# FPGA.net
KiCad netlist of a schematic drawn in Altium Designer
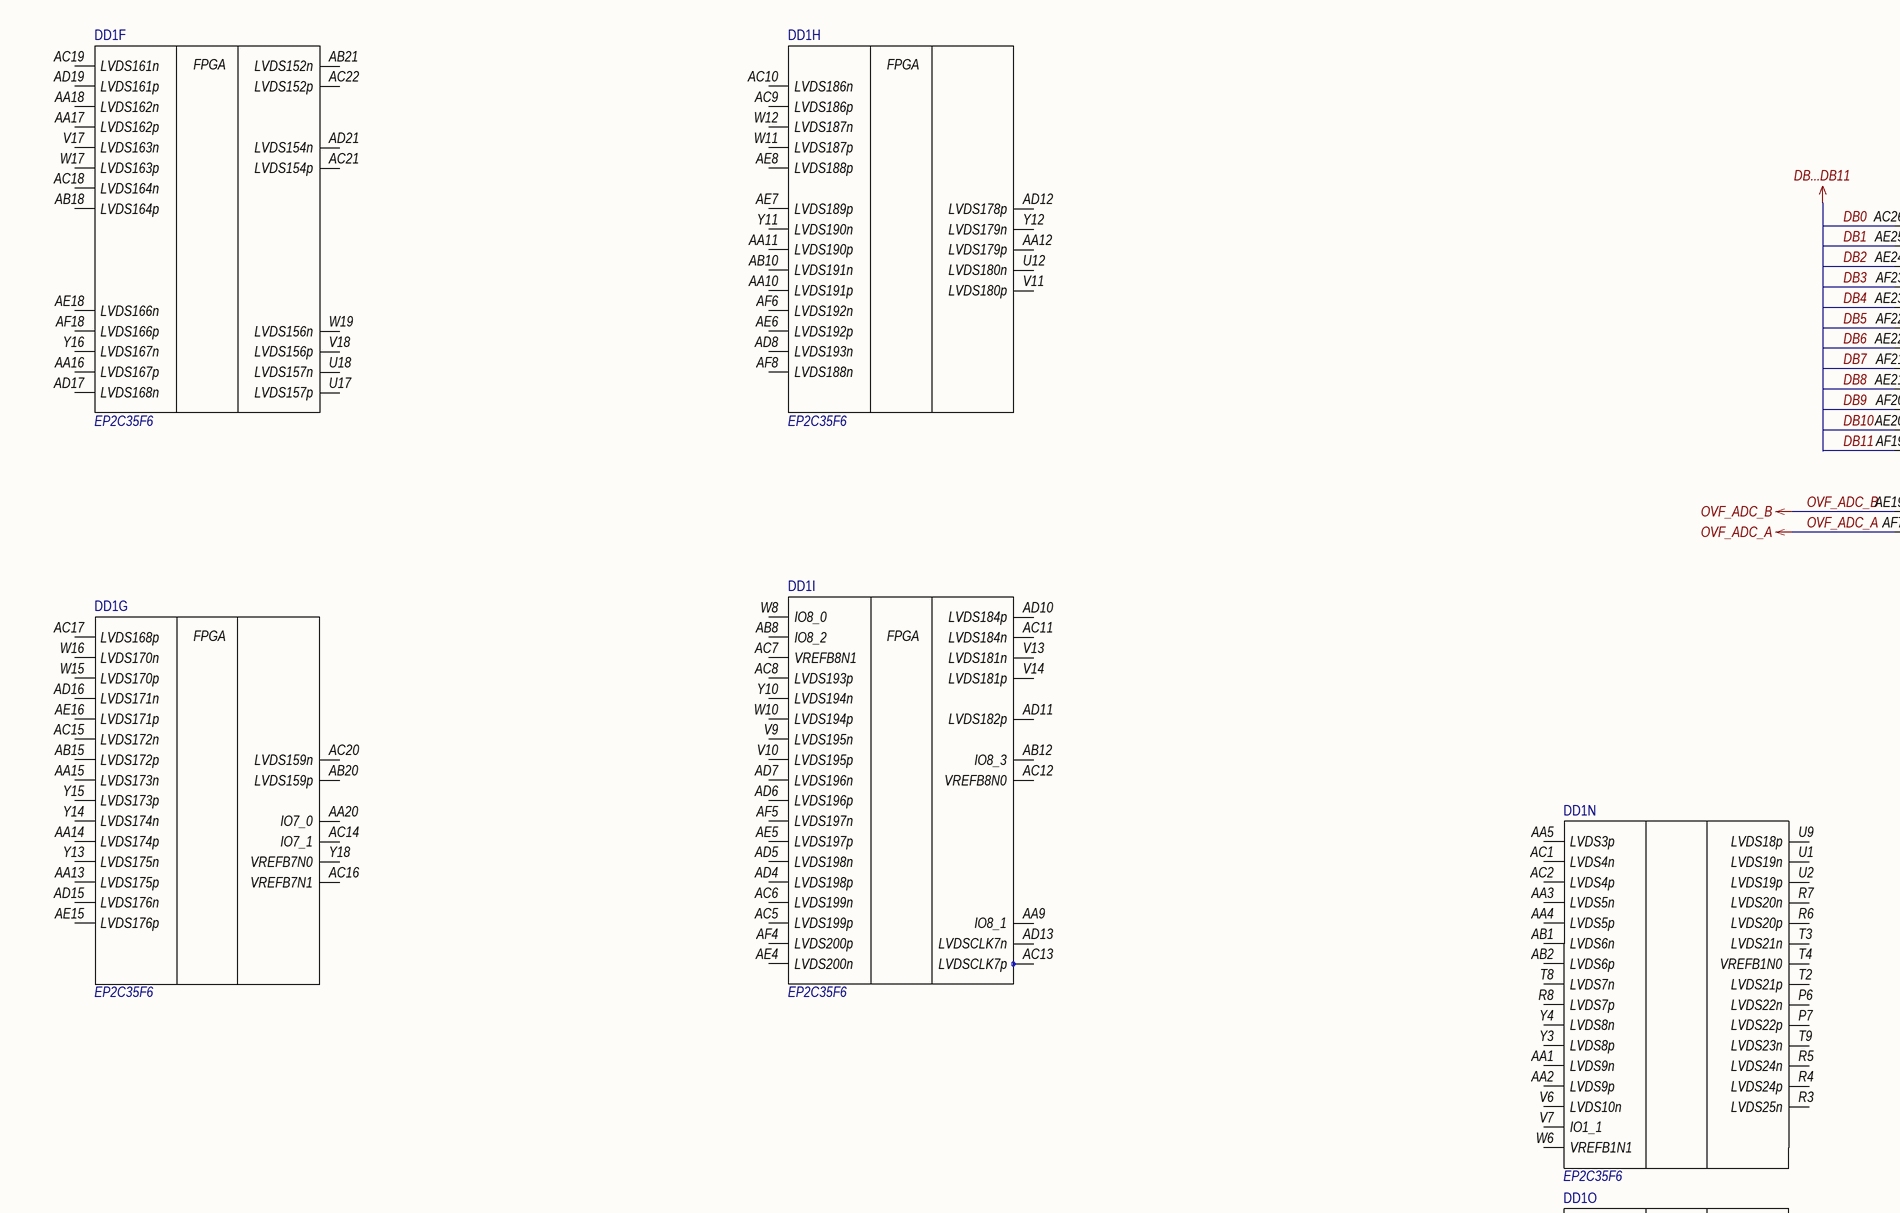
[diagram p0: FPGA.SchDoc, top left]
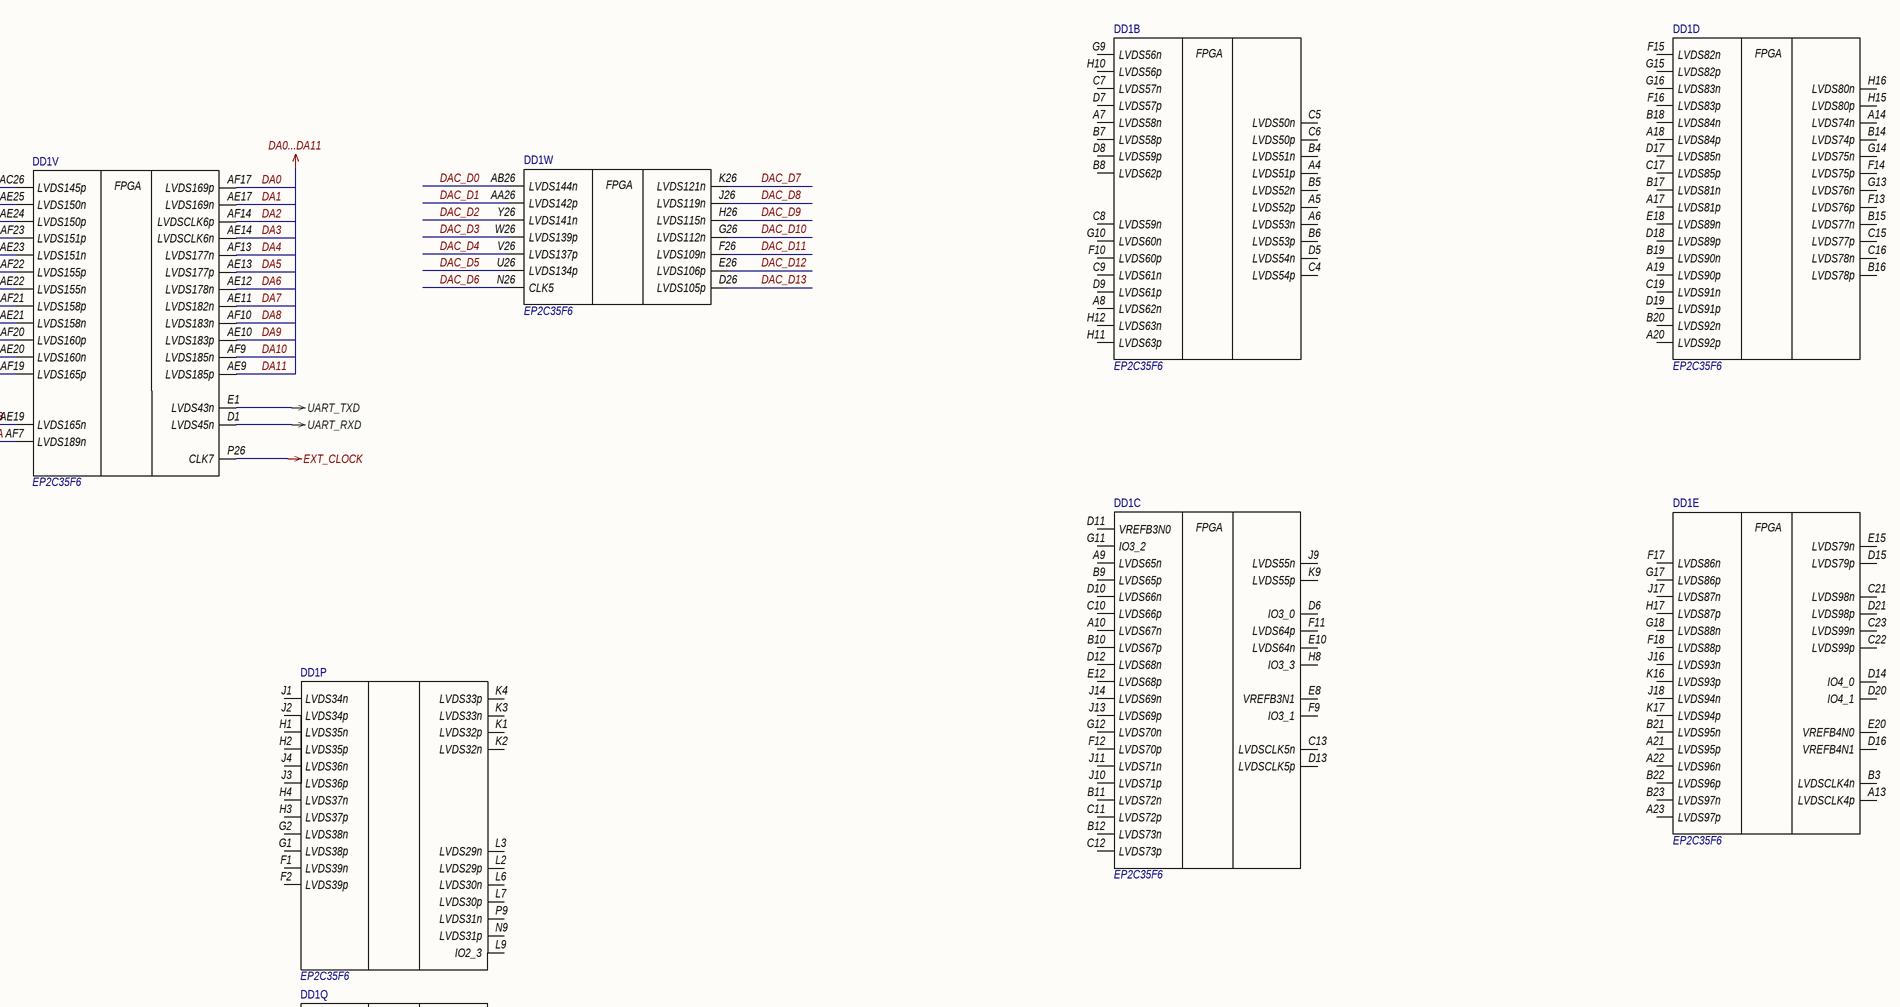
[diagram p1: FPGA.SchDoc, top right]
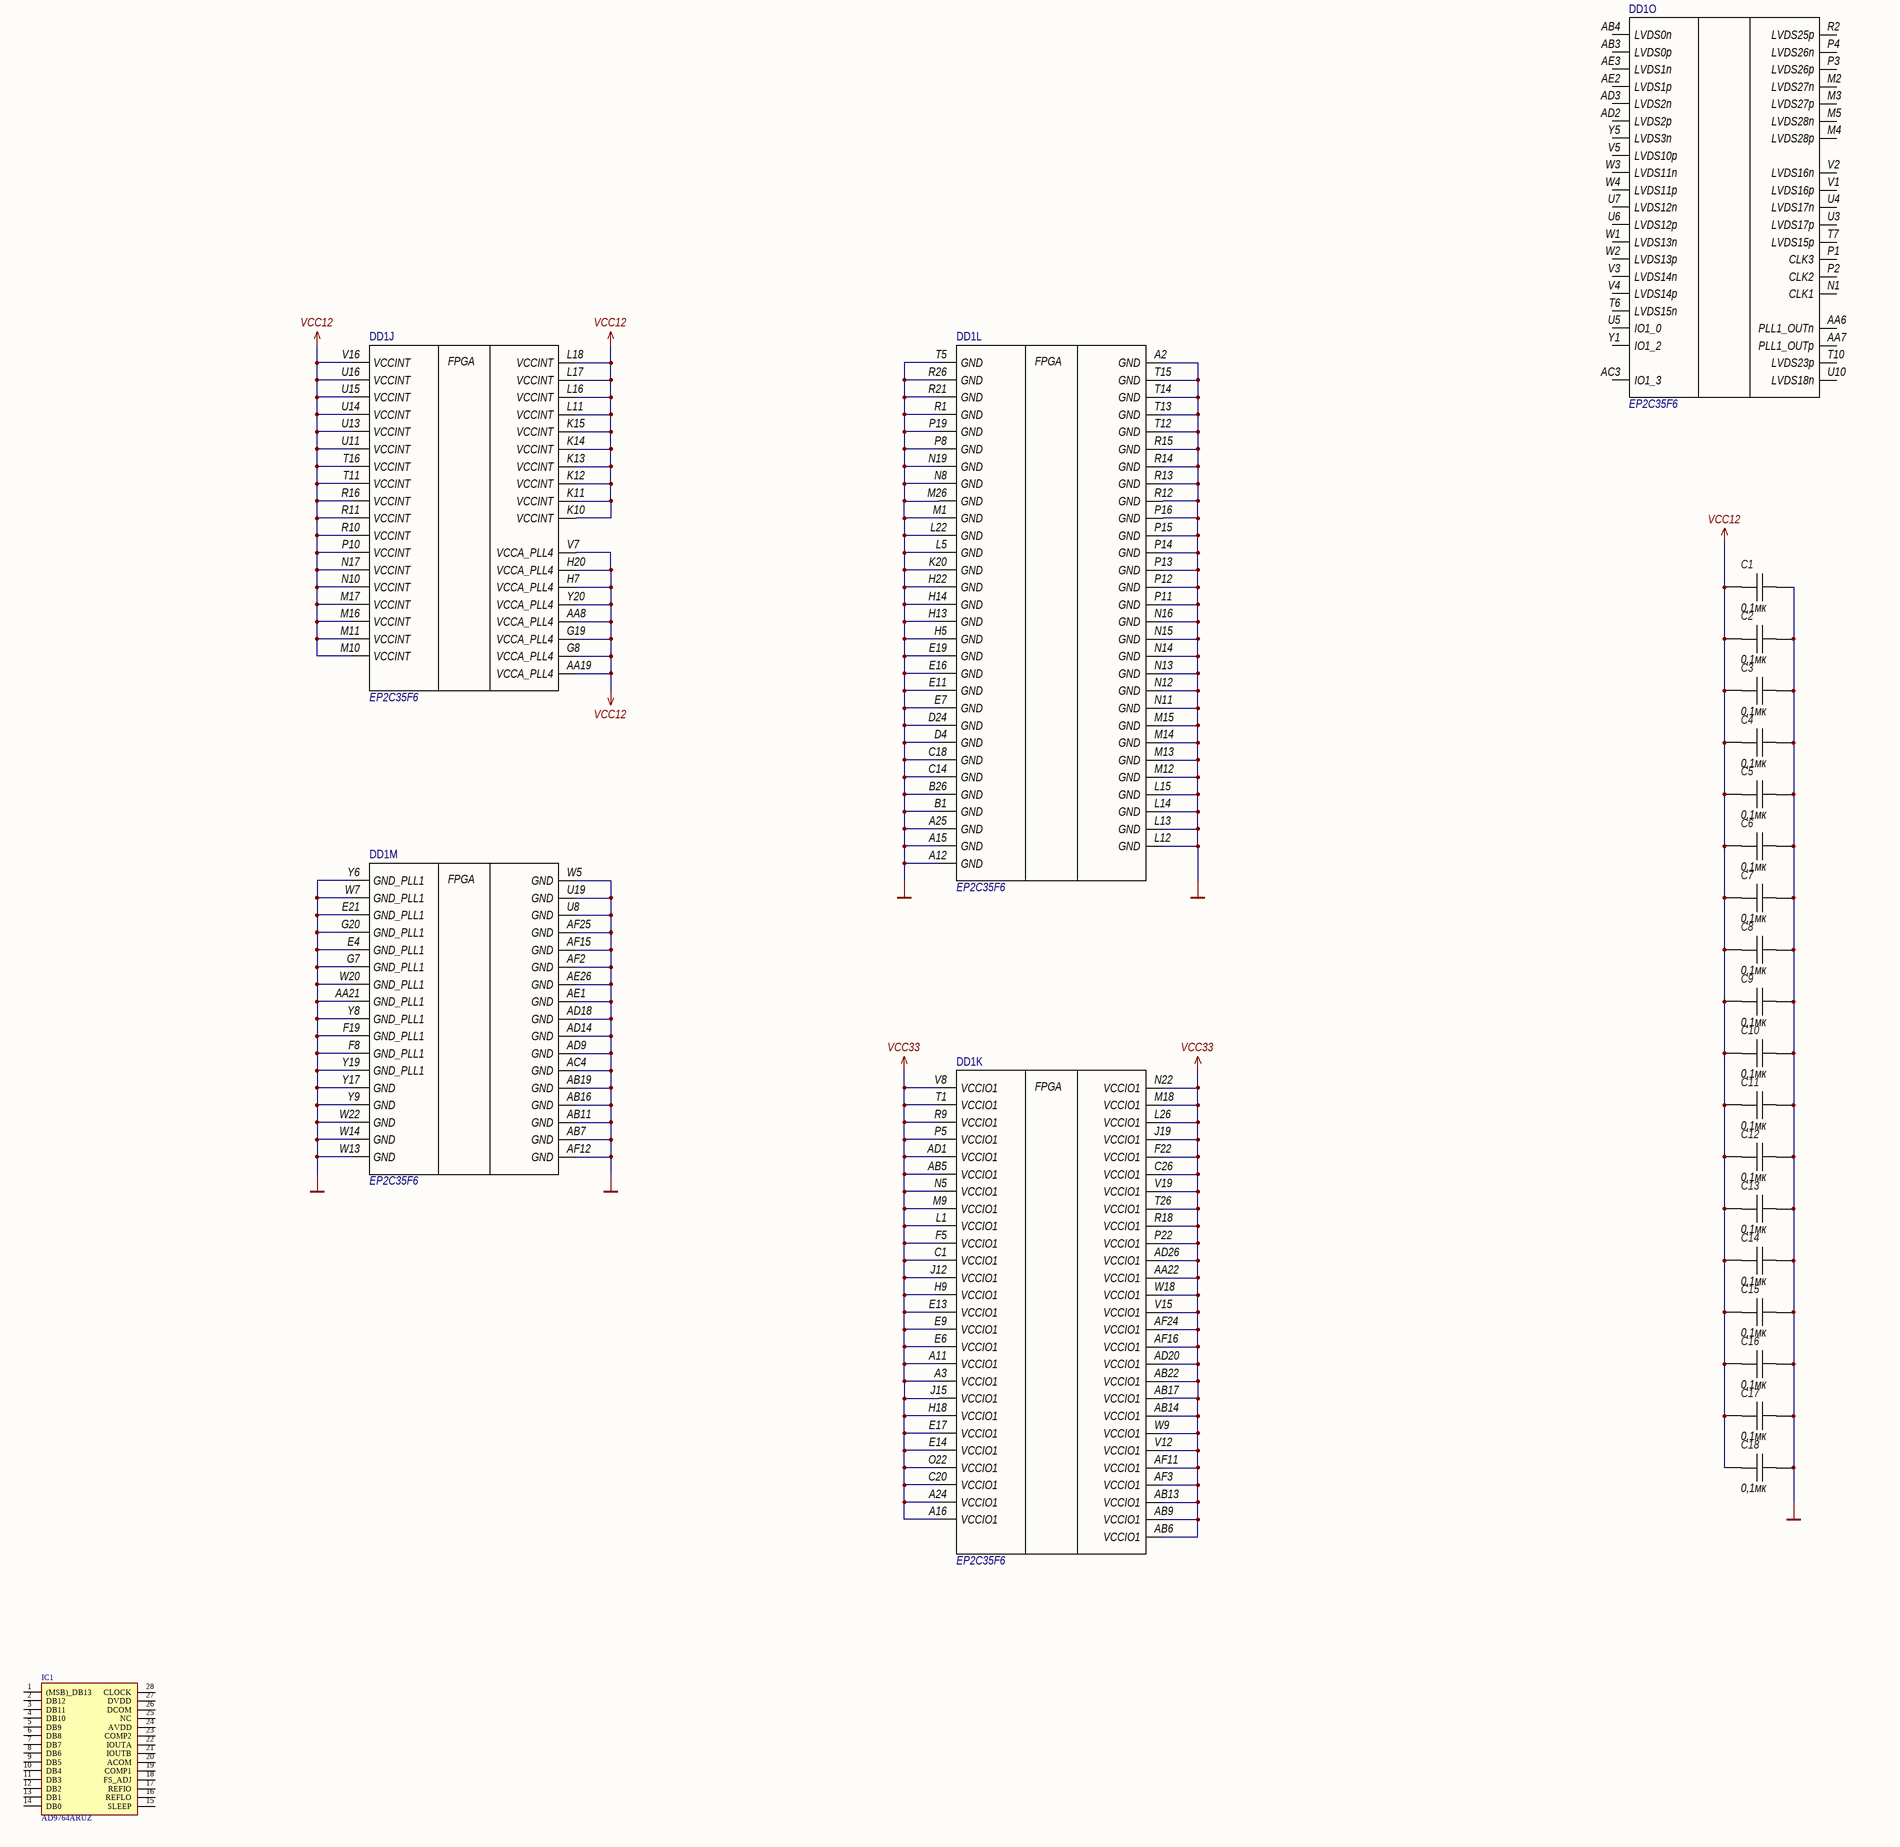
[diagram p2: FPGA.SchDoc, bottom left]
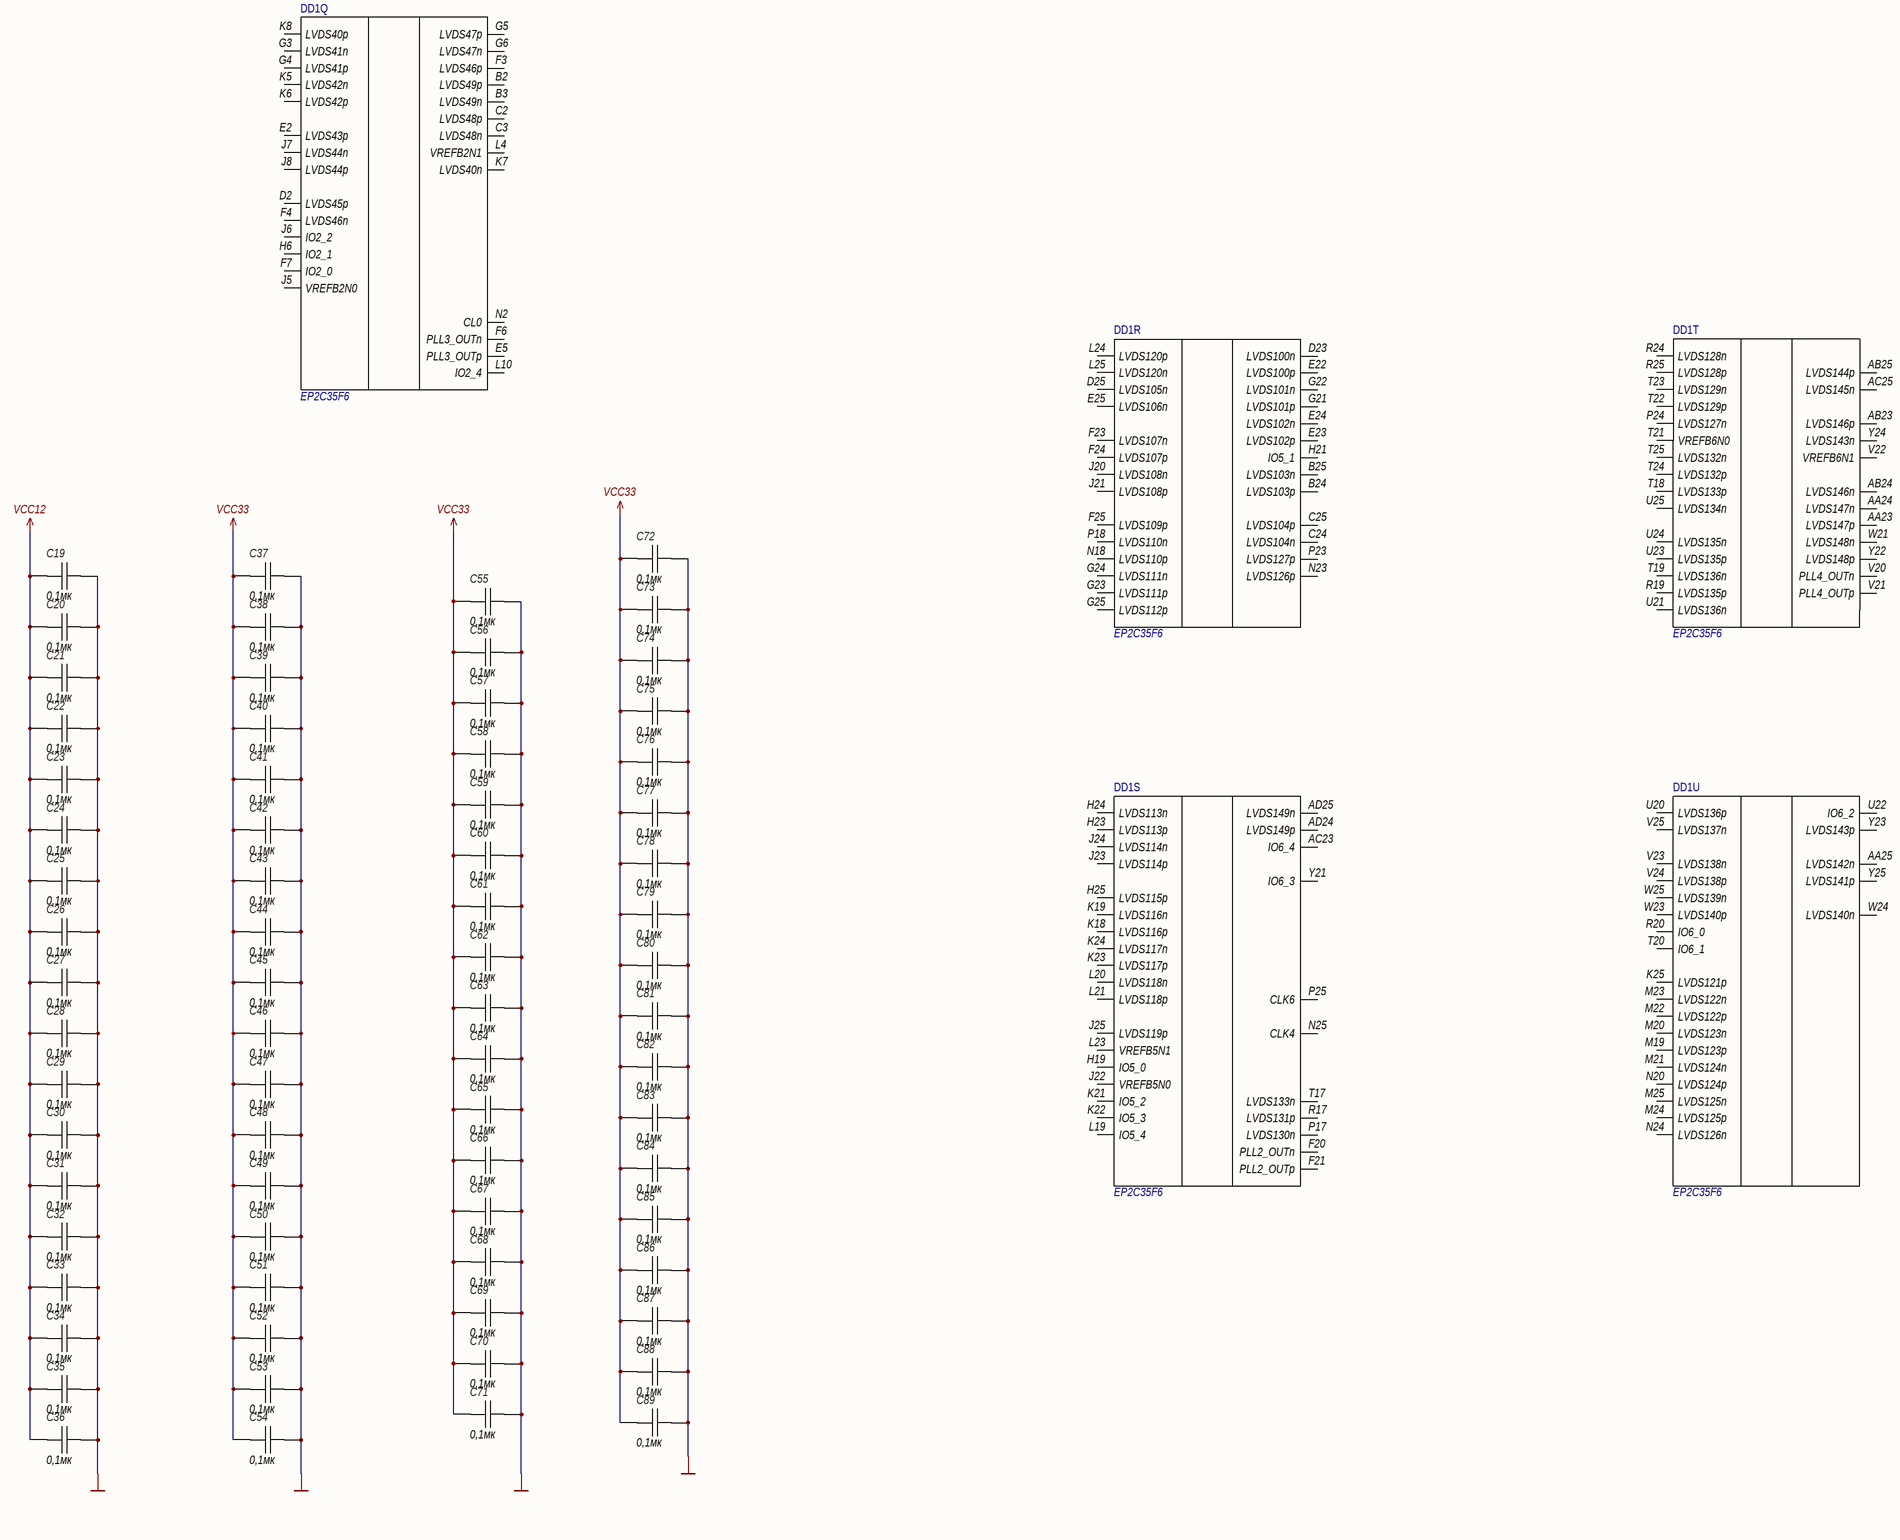
[diagram p3: FPGA.SchDoc, bottom right]

(export (version "E")
  (design (tool "Eeschema 10.0.6"))
  (components
    (comp (ref "C1")
      (value "0,1мк")
      (footprint "RESC1005X35N")
      (libsource (lib "FPGA_Automotibe_Radar_Lib") (part "Capacitor_0.1u"))
    )
    (comp (ref "C2")
      (value "0,1мк")
      (footprint "RESC1005X35N")
      (libsource (lib "FPGA_Automotibe_Radar_Lib") (part "Capacitor_0.1u"))
    )
    (comp (ref "C3")
      (value "0,1мк")
      (footprint "RESC1005X35N")
      (libsource (lib "FPGA_Automotibe_Radar_Lib") (part "Capacitor_0.1u"))
    )
    (comp (ref "C4")
      (value "0,1мк")
      (footprint "RESC1005X35N")
      (libsource (lib "FPGA_Automotibe_Radar_Lib") (part "Capacitor_0.1u"))
    )
    (comp (ref "C5")
      (value "0,1мк")
      (footprint "RESC1005X35N")
      (libsource (lib "FPGA_Automotibe_Radar_Lib") (part "Capacitor_0.1u"))
    )
    (comp (ref "C6")
      (value "0,1мк")
      (footprint "RESC1005X35N")
      (libsource (lib "FPGA_Automotibe_Radar_Lib") (part "Capacitor_0.1u"))
    )
    (comp (ref "C7")
      (value "0,1мк")
      (footprint "RESC1005X35N")
      (libsource (lib "FPGA_Automotibe_Radar_Lib") (part "Capacitor_0.1u"))
    )
    (comp (ref "C8")
      (value "0,1мк")
      (footprint "RESC1005X35N")
      (libsource (lib "FPGA_Automotibe_Radar_Lib") (part "Capacitor_0.1u"))
    )
    (comp (ref "C9")
      (value "0,1мк")
      (footprint "RESC1005X35N")
      (libsource (lib "FPGA_Automotibe_Radar_Lib") (part "Capacitor_0.1u"))
    )
    (comp (ref "C10")
      (value "0,1мк")
      (footprint "RESC1005X35N")
      (libsource (lib "FPGA_Automotibe_Radar_Lib") (part "Capacitor_0.1u"))
    )
    (comp (ref "C11")
      (value "0,1мк")
      (footprint "RESC1005X35N")
      (libsource (lib "FPGA_Automotibe_Radar_Lib") (part "Capacitor_0.1u"))
    )
    (comp (ref "C12")
      (value "0,1мк")
      (footprint "RESC1005X35N")
      (libsource (lib "FPGA_Automotibe_Radar_Lib") (part "Capacitor_0.1u"))
    )
    (comp (ref "C13")
      (value "0,1мк")
      (footprint "RESC1005X35N")
      (libsource (lib "FPGA_Automotibe_Radar_Lib") (part "Capacitor_0.1u"))
    )
    (comp (ref "C14")
      (value "0,1мк")
      (footprint "RESC1005X35N")
      (libsource (lib "FPGA_Automotibe_Radar_Lib") (part "Capacitor_0.1u"))
    )
    (comp (ref "C15")
      (value "0,1мк")
      (footprint "RESC1005X35N")
      (libsource (lib "FPGA_Automotibe_Radar_Lib") (part "Capacitor_0.1u"))
    )
    (comp (ref "C16")
      (value "0,1мк")
      (footprint "RESC1005X35N")
      (libsource (lib "FPGA_Automotibe_Radar_Lib") (part "Capacitor_0.1u"))
    )
    (comp (ref "C17")
      (value "0,1мк")
      (footprint "RESC1005X35N")
      (libsource (lib "FPGA_Automotibe_Radar_Lib") (part "Capacitor_0.1u"))
    )
    (comp (ref "C18")
      (value "0,1мк")
      (footprint "RESC1005X35N")
      (libsource (lib "FPGA_Automotibe_Radar_Lib") (part "Capacitor_0.1u"))
    )
    (comp (ref "C19")
      (value "0,1мк")
      (footprint "RESC1005X35N")
      (libsource (lib "FPGA_Automotibe_Radar_Lib") (part "Capacitor_0.1u"))
    )
    (comp (ref "C20")
      (value "0,1мк")
      (footprint "RESC1005X35N")
      (libsource (lib "FPGA_Automotibe_Radar_Lib") (part "Capacitor_0.1u"))
    )
    (comp (ref "C21")
      (value "0,1мк")
      (footprint "RESC1005X35N")
      (libsource (lib "FPGA_Automotibe_Radar_Lib") (part "Capacitor_0.1u"))
    )
    (comp (ref "C22")
      (value "0,1мк")
      (footprint "RESC1005X35N")
      (libsource (lib "FPGA_Automotibe_Radar_Lib") (part "Capacitor_0.1u"))
    )
    (comp (ref "C23")
      (value "0,1мк")
      (footprint "RESC1005X35N")
      (libsource (lib "FPGA_Automotibe_Radar_Lib") (part "Capacitor_0.1u"))
    )
    (comp (ref "C24")
      (value "0,1мк")
      (footprint "RESC1005X35N")
      (libsource (lib "FPGA_Automotibe_Radar_Lib") (part "Capacitor_0.1u"))
    )
    (comp (ref "C25")
      (value "0,1мк")
      (footprint "RESC1005X35N")
      (libsource (lib "FPGA_Automotibe_Radar_Lib") (part "Capacitor_0.1u"))
    )
    (comp (ref "C26")
      (value "0,1мк")
      (footprint "RESC1005X35N")
      (libsource (lib "FPGA_Automotibe_Radar_Lib") (part "Capacitor_0.1u"))
    )
    (comp (ref "C27")
      (value "0,1мк")
      (footprint "RESC1005X35N")
      (libsource (lib "FPGA_Automotibe_Radar_Lib") (part "Capacitor_0.1u"))
    )
    (comp (ref "C28")
      (value "0,1мк")
      (footprint "RESC1005X35N")
      (libsource (lib "FPGA_Automotibe_Radar_Lib") (part "Capacitor_0.1u"))
    )
    (comp (ref "C29")
      (value "0,1мк")
      (footprint "RESC1005X35N")
      (libsource (lib "FPGA_Automotibe_Radar_Lib") (part "Capacitor_0.1u"))
    )
    (comp (ref "C30")
      (value "0,1мк")
      (footprint "RESC1005X35N")
      (libsource (lib "FPGA_Automotibe_Radar_Lib") (part "Capacitor_0.1u"))
    )
    (comp (ref "C31")
      (value "0,1мк")
      (footprint "RESC1005X35N")
      (libsource (lib "FPGA_Automotibe_Radar_Lib") (part "Capacitor_0.1u"))
    )
    (comp (ref "C32")
      (value "0,1мк")
      (footprint "RESC1005X35N")
      (libsource (lib "FPGA_Automotibe_Radar_Lib") (part "Capacitor_0.1u"))
    )
    (comp (ref "C33")
      (value "0,1мк")
      (footprint "RESC1005X35N")
      (libsource (lib "FPGA_Automotibe_Radar_Lib") (part "Capacitor_0.1u"))
    )
    (comp (ref "C34")
      (value "0,1мк")
      (footprint "RESC1005X35N")
      (libsource (lib "FPGA_Automotibe_Radar_Lib") (part "Capacitor_0.1u"))
    )
    (comp (ref "C35")
      (value "0,1мк")
      (footprint "RESC1005X35N")
      (libsource (lib "FPGA_Automotibe_Radar_Lib") (part "Capacitor_0.1u"))
    )
    (comp (ref "C36")
      (value "0,1мк")
      (footprint "RESC1005X35N")
      (libsource (lib "FPGA_Automotibe_Radar_Lib") (part "Capacitor_0.1u"))
    )
    (comp (ref "C37")
      (value "0,1мк")
      (footprint "RESC1005X35N")
      (libsource (lib "FPGA_Automotibe_Radar_Lib") (part "Capacitor_0.1u"))
    )
    (comp (ref "C38")
      (value "0,1мк")
      (footprint "RESC1005X35N")
      (libsource (lib "FPGA_Automotibe_Radar_Lib") (part "Capacitor_0.1u"))
    )
    (comp (ref "C39")
      (value "0,1мк")
      (footprint "RESC1005X35N")
      (libsource (lib "FPGA_Automotibe_Radar_Lib") (part "Capacitor_0.1u"))
    )
    (comp (ref "C40")
      (value "0,1мк")
      (footprint "RESC1005X35N")
      (libsource (lib "FPGA_Automotibe_Radar_Lib") (part "Capacitor_0.1u"))
    )
    (comp (ref "C41")
      (value "0,1мк")
      (footprint "RESC1005X35N")
      (libsource (lib "FPGA_Automotibe_Radar_Lib") (part "Capacitor_0.1u"))
    )
    (comp (ref "C42")
      (value "0,1мк")
      (footprint "RESC1005X35N")
      (libsource (lib "FPGA_Automotibe_Radar_Lib") (part "Capacitor_0.1u"))
    )
    (comp (ref "C43")
      (value "0,1мк")
      (footprint "RESC1005X35N")
      (libsource (lib "FPGA_Automotibe_Radar_Lib") (part "Capacitor_0.1u"))
    )
    (comp (ref "C44")
      (value "0,1мк")
      (footprint "RESC1005X35N")
      (libsource (lib "FPGA_Automotibe_Radar_Lib") (part "Capacitor_0.1u"))
    )
    (comp (ref "C45")
      (value "0,1мк")
      (footprint "RESC1005X35N")
      (libsource (lib "FPGA_Automotibe_Radar_Lib") (part "Capacitor_0.1u"))
    )
    (comp (ref "C46")
      (value "0,1мк")
      (footprint "RESC1005X35N")
      (libsource (lib "FPGA_Automotibe_Radar_Lib") (part "Capacitor_0.1u"))
    )
    (comp (ref "C47")
      (value "0,1мк")
      (footprint "RESC1005X35N")
      (libsource (lib "FPGA_Automotibe_Radar_Lib") (part "Capacitor_0.1u"))
    )
    (comp (ref "C48")
      (value "0,1мк")
      (footprint "RESC1005X35N")
      (libsource (lib "FPGA_Automotibe_Radar_Lib") (part "Capacitor_0.1u"))
    )
    (comp (ref "C49")
      (value "0,1мк")
      (footprint "RESC1005X35N")
      (libsource (lib "FPGA_Automotibe_Radar_Lib") (part "Capacitor_0.1u"))
    )
    (comp (ref "C50")
      (value "0,1мк")
      (footprint "RESC1005X35N")
      (libsource (lib "FPGA_Automotibe_Radar_Lib") (part "Capacitor_0.1u"))
    )
    (comp (ref "C51")
      (value "0,1мк")
      (footprint "RESC1005X35N")
      (libsource (lib "FPGA_Automotibe_Radar_Lib") (part "Capacitor_0.1u"))
    )
    (comp (ref "C52")
      (value "0,1мк")
      (footprint "RESC1005X35N")
      (libsource (lib "FPGA_Automotibe_Radar_Lib") (part "Capacitor_0.1u"))
    )
    (comp (ref "C53")
      (value "0,1мк")
      (footprint "RESC1005X35N")
      (libsource (lib "FPGA_Automotibe_Radar_Lib") (part "Capacitor_0.1u"))
    )
    (comp (ref "C54")
      (value "0,1мк")
      (footprint "RESC1005X35N")
      (libsource (lib "FPGA_Automotibe_Radar_Lib") (part "Capacitor_0.1u"))
    )
    (comp (ref "C55")
      (value "0,1мк")
      (footprint "RESC1005X35N")
      (libsource (lib "FPGA_Automotibe_Radar_Lib") (part "Capacitor_0.1u"))
    )
    (comp (ref "C56")
      (value "0,1мк")
      (footprint "RESC1005X35N")
      (libsource (lib "FPGA_Automotibe_Radar_Lib") (part "Capacitor_0.1u"))
    )
    (comp (ref "C57")
      (value "0,1мк")
      (footprint "RESC1005X35N")
      (libsource (lib "FPGA_Automotibe_Radar_Lib") (part "Capacitor_0.1u"))
    )
    (comp (ref "C58")
      (value "0,1мк")
      (footprint "RESC1005X35N")
      (libsource (lib "FPGA_Automotibe_Radar_Lib") (part "Capacitor_0.1u"))
    )
    (comp (ref "C59")
      (value "0,1мк")
      (footprint "RESC1005X35N")
      (libsource (lib "FPGA_Automotibe_Radar_Lib") (part "Capacitor_0.1u"))
    )
    (comp (ref "C60")
      (value "0,1мк")
      (footprint "RESC1005X35N")
      (libsource (lib "FPGA_Automotibe_Radar_Lib") (part "Capacitor_0.1u"))
    )
    (comp (ref "C61")
      (value "0,1мк")
      (footprint "RESC1005X35N")
      (libsource (lib "FPGA_Automotibe_Radar_Lib") (part "Capacitor_0.1u"))
    )
    (comp (ref "C62")
      (value "0,1мк")
      (footprint "RESC1005X35N")
      (libsource (lib "FPGA_Automotibe_Radar_Lib") (part "Capacitor_0.1u"))
    )
    (comp (ref "C63")
      (value "0,1мк")
      (footprint "RESC1005X35N")
      (libsource (lib "FPGA_Automotibe_Radar_Lib") (part "Capacitor_0.1u"))
    )
    (comp (ref "C64")
      (value "0,1мк")
      (footprint "RESC1005X35N")
      (libsource (lib "FPGA_Automotibe_Radar_Lib") (part "Capacitor_0.1u"))
    )
    (comp (ref "C65")
      (value "0,1мк")
      (footprint "RESC1005X35N")
      (libsource (lib "FPGA_Automotibe_Radar_Lib") (part "Capacitor_0.1u"))
    )
    (comp (ref "C66")
      (value "0,1мк")
      (footprint "RESC1005X35N")
      (libsource (lib "FPGA_Automotibe_Radar_Lib") (part "Capacitor_0.1u"))
    )
    (comp (ref "C67")
      (value "0,1мк")
      (footprint "RESC1005X35N")
      (libsource (lib "FPGA_Automotibe_Radar_Lib") (part "Capacitor_0.1u"))
    )
    (comp (ref "C68")
      (value "0,1мк")
      (footprint "RESC1005X35N")
      (libsource (lib "FPGA_Automotibe_Radar_Lib") (part "Capacitor_0.1u"))
    )
    (comp (ref "C69")
      (value "0,1мк")
      (footprint "RESC1005X35N")
      (libsource (lib "FPGA_Automotibe_Radar_Lib") (part "Capacitor_0.1u"))
    )
    (comp (ref "C70")
      (value "0,1мк")
      (footprint "RESC1005X35N")
      (libsource (lib "FPGA_Automotibe_Radar_Lib") (part "Capacitor_0.1u"))
    )
    (comp (ref "C71")
      (value "0,1мк")
      (footprint "RESC1005X35N")
      (libsource (lib "FPGA_Automotibe_Radar_Lib") (part "Capacitor_0.1u"))
    )
    (comp (ref "C72")
      (value "0,1мк")
      (footprint "RESC1005X35N")
      (libsource (lib "FPGA_Automotibe_Radar_Lib") (part "Capacitor_0.1u"))
    )
    (comp (ref "C73")
      (value "0,1мк")
      (footprint "RESC1005X35N")
      (libsource (lib "FPGA_Automotibe_Radar_Lib") (part "Capacitor_0.1u"))
    )
    (comp (ref "C74")
      (value "0,1мк")
      (footprint "RESC1005X35N")
      (libsource (lib "FPGA_Automotibe_Radar_Lib") (part "Capacitor_0.1u"))
    )
    (comp (ref "C75")
      (value "0,1мк")
      (footprint "RESC1005X35N")
      (libsource (lib "FPGA_Automotibe_Radar_Lib") (part "Capacitor_0.1u"))
    )
    (comp (ref "C76")
      (value "0,1мк")
      (footprint "RESC1005X35N")
      (libsource (lib "FPGA_Automotibe_Radar_Lib") (part "Capacitor_0.1u"))
    )
    (comp (ref "C77")
      (value "0,1мк")
      (footprint "RESC1005X35N")
      (libsource (lib "FPGA_Automotibe_Radar_Lib") (part "Capacitor_0.1u"))
    )
    (comp (ref "C78")
      (value "0,1мк")
      (footprint "RESC1005X35N")
      (libsource (lib "FPGA_Automotibe_Radar_Lib") (part "Capacitor_0.1u"))
    )
    (comp (ref "C79")
      (value "0,1мк")
      (footprint "RESC1005X35N")
      (libsource (lib "FPGA_Automotibe_Radar_Lib") (part "Capacitor_0.1u"))
    )
    (comp (ref "C80")
      (value "0,1мк")
      (footprint "RESC1005X35N")
      (libsource (lib "FPGA_Automotibe_Radar_Lib") (part "Capacitor_0.1u"))
    )
    (comp (ref "C81")
      (value "0,1мк")
      (footprint "RESC1005X35N")
      (libsource (lib "FPGA_Automotibe_Radar_Lib") (part "Capacitor_0.1u"))
    )
    (comp (ref "C82")
      (value "0,1мк")
      (footprint "RESC1005X35N")
      (libsource (lib "FPGA_Automotibe_Radar_Lib") (part "Capacitor_0.1u"))
    )
    (comp (ref "C83")
      (value "0,1мк")
      (footprint "RESC1005X35N")
      (libsource (lib "FPGA_Automotibe_Radar_Lib") (part "Capacitor_0.1u"))
    )
    (comp (ref "C84")
      (value "0,1мк")
      (footprint "RESC1005X35N")
      (libsource (lib "FPGA_Automotibe_Radar_Lib") (part "Capacitor_0.1u"))
    )
    (comp (ref "C85")
      (value "0,1мк")
      (footprint "RESC1005X35N")
      (libsource (lib "FPGA_Automotibe_Radar_Lib") (part "Capacitor_0.1u"))
    )
    (comp (ref "C86")
      (value "0,1мк")
      (footprint "RESC1005X35N")
      (libsource (lib "FPGA_Automotibe_Radar_Lib") (part "Capacitor_0.1u"))
    )
    (comp (ref "C87")
      (value "0,1мк")
      (footprint "RESC1005X35N")
      (libsource (lib "FPGA_Automotibe_Radar_Lib") (part "Capacitor_0.1u"))
    )
    (comp (ref "C88")
      (value "0,1мк")
      (footprint "RESC1005X35N")
      (libsource (lib "FPGA_Automotibe_Radar_Lib") (part "Capacitor_0.1u"))
    )
    (comp (ref "C89")
      (value "0,1мк")
      (footprint "RESC1005X35N")
      (libsource (lib "FPGA_Automotibe_Radar_Lib") (part "Capacitor_0.1u"))
    )
    (comp (ref "DD1")
      (value "EP2C35F6")
      (footprint "BGA672CP100_26X26_2700X2700X240B60N")
      (libsource (lib "FPGA_Automotibe_Radar_Lib") (part "PLIS"))
    )
    (comp (ref "IC1")
      (value "AD9764ARUZ")
      (footprint "SamacSys:SOP65P640X120-28N")
      (description "Integrated Circuit")
      (fields (field (name "MOUSER PART NUMBER") "584-AD9764ARUZ"))
      (libsource (lib "*") (part "AD9764ARUZ"))
    )
  )
  (nets
    (net (code "1") (name "/DA0") (class "Default")
      (node (ref "DD1") (pin "AF17") (pinfunction "LVDS169p_AF17") (pintype "passive"))
    )
    (net (code "2") (name "/DA1") (class "Default")
      (node (ref "DD1") (pin "AE17") (pinfunction "LVDS169n_AE17") (pintype "passive"))
    )
    (net (code "3") (name "/DA2") (class "Default")
      (node (ref "DD1") (pin "AF14") (pinfunction "LVDSCLK6p_AF14") (pintype "passive"))
    )
    (net (code "4") (name "/DA3") (class "Default")
      (node (ref "DD1") (pin "AE14") (pinfunction "LVDSCLK6n_AE14") (pintype "passive"))
    )
    (net (code "5") (name "/DA4") (class "Default")
      (node (ref "DD1") (pin "AF13") (pinfunction "LVDS177n_AF13") (pintype "passive"))
    )
    (net (code "6") (name "/DA5") (class "Default")
      (node (ref "DD1") (pin "AE13") (pinfunction "LVDS177p_AE13") (pintype "passive"))
    )
    (net (code "7") (name "/DA6") (class "Default")
      (node (ref "DD1") (pin "AE12") (pinfunction "LVDS178n_AE12") (pintype "passive"))
    )
    (net (code "8") (name "/DA7") (class "Default")
      (node (ref "DD1") (pin "AE11") (pinfunction "LVDS182n_AE11") (pintype "passive"))
    )
    (net (code "9") (name "/DA8") (class "Default")
      (node (ref "DD1") (pin "AF10") (pinfunction "LVDS183n_AF10") (pintype "passive"))
    )
    (net (code "10") (name "/DA9") (class "Default")
      (node (ref "DD1") (pin "AE10") (pinfunction "LVDS183p_AE10") (pintype "passive"))
    )
    (net (code "11") (name "/DA10") (class "Default")
      (node (ref "DD1") (pin "AF9") (pinfunction "LVDS185n_AF9") (pintype "passive"))
    )
    (net (code "12") (name "/DA11") (class "Default")
      (node (ref "DD1") (pin "AE9") (pinfunction "LVDS185p_AE9") (pintype "passive"))
    )
    (net (code "13") (name "/DAC_D0") (class "Default")
      (node (ref "DD1") (pin "AB26") (pinfunction "LVDS144n_AB26") (pintype "passive"))
    )
    (net (code "14") (name "/DAC_D1") (class "Default")
      (node (ref "DD1") (pin "AA26") (pinfunction "LVDS142p_AA26") (pintype "passive"))
    )
    (net (code "15") (name "/DAC_D2") (class "Default")
      (node (ref "DD1") (pin "Y26") (pinfunction "LVDS141n_Y26") (pintype "passive"))
    )
    (net (code "16") (name "/DAC_D3") (class "Default")
      (node (ref "DD1") (pin "W26") (pinfunction "LVDS139p_W26") (pintype "passive"))
    )
    (net (code "17") (name "/DAC_D4") (class "Default")
      (node (ref "DD1") (pin "V26") (pinfunction "LVDS137p_V26") (pintype "passive"))
    )
    (net (code "18") (name "/DAC_D5") (class "Default")
      (node (ref "DD1") (pin "U26") (pinfunction "LVDS134p_U26") (pintype "passive"))
    )
    (net (code "19") (name "/DAC_D6") (class "Default")
      (node (ref "DD1") (pin "N26") (pinfunction "CLK5_N26") (pintype "passive"))
    )
    (net (code "20") (name "/DAC_D7") (class "Default")
      (node (ref "DD1") (pin "K26") (pinfunction "LVDS121n_K26") (pintype "passive"))
    )
    (net (code "21") (name "/DAC_D8") (class "Default")
      (node (ref "DD1") (pin "J26") (pinfunction "LVDS119n_J26") (pintype "passive"))
    )
    (net (code "22") (name "/DAC_D9") (class "Default")
      (node (ref "DD1") (pin "H26") (pinfunction "LVDS115n_H26") (pintype "passive"))
    )
    (net (code "23") (name "/DAC_D10") (class "Default")
      (node (ref "DD1") (pin "G26") (pinfunction "LVDS112n_G26") (pintype "passive"))
    )
    (net (code "24") (name "/DAC_D11") (class "Default")
      (node (ref "DD1") (pin "F26") (pinfunction "LVDS109n_F26") (pintype "passive"))
    )
    (net (code "25") (name "/DAC_D12") (class "Default")
      (node (ref "DD1") (pin "E26") (pinfunction "LVDS106p_E26") (pintype "passive"))
    )
    (net (code "26") (name "/DAC_D13") (class "Default")
      (node (ref "DD1") (pin "D26") (pinfunction "LVDS105p_D26") (pintype "passive"))
    )
    (net (code "27") (name "/DB0") (class "Default")
      (node (ref "DD1") (pin "AC26") (pinfunction "LVDS145p_AC26") (pintype "passive"))
    )
    (net (code "28") (name "/DB1") (class "Default")
      (node (ref "DD1") (pin "AE25") (pinfunction "LVDS150n_AE25") (pintype "passive"))
    )
    (net (code "29") (name "/DB2") (class "Default")
      (node (ref "DD1") (pin "AE24") (pinfunction "LVDS150p_AE24") (pintype "passive"))
    )
    (net (code "30") (name "/DB3") (class "Default")
      (node (ref "DD1") (pin "AF23") (pinfunction "LVDS151p_AF23") (pintype "passive"))
    )
    (net (code "31") (name "/DB4") (class "Default")
      (node (ref "DD1") (pin "AE23") (pinfunction "LVDS151n_AE23") (pintype "passive"))
    )
    (net (code "32") (name "/DB5") (class "Default")
      (node (ref "DD1") (pin "AF22") (pinfunction "LVDS155p_AF22") (pintype "passive"))
    )
    (net (code "33") (name "/DB6") (class "Default")
      (node (ref "DD1") (pin "AE22") (pinfunction "LVDS155n_AE22") (pintype "passive"))
    )
    (net (code "34") (name "/DB7") (class "Default")
      (node (ref "DD1") (pin "AF21") (pinfunction "LVDS158p_AF21") (pintype "passive"))
    )
    (net (code "35") (name "/DB8") (class "Default")
      (node (ref "DD1") (pin "AE21") (pinfunction "LVDS158n_AE21") (pintype "passive"))
    )
    (net (code "36") (name "/DB9") (class "Default")
      (node (ref "DD1") (pin "AF20") (pinfunction "LVDS160p_AF20") (pintype "passive"))
    )
    (net (code "37") (name "/DB10") (class "Default")
      (node (ref "DD1") (pin "AE20") (pinfunction "LVDS160n_AE20") (pintype "passive"))
    )
    (net (code "38") (name "/DB11") (class "Default")
      (node (ref "DD1") (pin "AF19") (pinfunction "LVDS165p_AF19") (pintype "passive"))
    )
    (net (code "41") (name "EXT_CLOCK") (class "Default")
      (node (ref "DD1") (pin "P26") (pinfunction "CLK7_P26") (pintype "passive"))
    )
    (net (code "42") (name "GND") (class "Default")
      (node (ref "C1") (pin "2") (pinfunction "2_2") (pintype "passive"))
      (node (ref "C10") (pin "2") (pinfunction "2_2") (pintype "passive"))
      (node (ref "C11") (pin "2") (pinfunction "2_2") (pintype "passive"))
      (node (ref "C12") (pin "2") (pinfunction "2_2") (pintype "passive"))
      (node (ref "C13") (pin "2") (pinfunction "2_2") (pintype "passive"))
      (node (ref "C14") (pin "2") (pinfunction "2_2") (pintype "passive"))
      (node (ref "C15") (pin "2") (pinfunction "2_2") (pintype "passive"))
      (node (ref "C16") (pin "2") (pinfunction "2_2") (pintype "passive"))
      (node (ref "C17") (pin "2") (pinfunction "2_2") (pintype "passive"))
      (node (ref "C18") (pin "2") (pinfunction "2_2") (pintype "passive"))
      (node (ref "C19") (pin "2") (pinfunction "2_2") (pintype "passive"))
      (node (ref "C2") (pin "2") (pinfunction "2_2") (pintype "passive"))
      (node (ref "C20") (pin "2") (pinfunction "2_2") (pintype "passive"))
      (node (ref "C21") (pin "2") (pinfunction "2_2") (pintype "passive"))
      (node (ref "C22") (pin "2") (pinfunction "2_2") (pintype "passive"))
      (node (ref "C23") (pin "2") (pinfunction "2_2") (pintype "passive"))
      (node (ref "C24") (pin "2") (pinfunction "2_2") (pintype "passive"))
      (node (ref "C25") (pin "2") (pinfunction "2_2") (pintype "passive"))
      (node (ref "C26") (pin "2") (pinfunction "2_2") (pintype "passive"))
      (node (ref "C27") (pin "2") (pinfunction "2_2") (pintype "passive"))
      (node (ref "C28") (pin "2") (pinfunction "2_2") (pintype "passive"))
      (node (ref "C29") (pin "2") (pinfunction "2_2") (pintype "passive"))
      (node (ref "C3") (pin "2") (pinfunction "2_2") (pintype "passive"))
      (node (ref "C30") (pin "2") (pinfunction "2_2") (pintype "passive"))
      (node (ref "C31") (pin "2") (pinfunction "2_2") (pintype "passive"))
      (node (ref "C32") (pin "2") (pinfunction "2_2") (pintype "passive"))
      (node (ref "C33") (pin "2") (pinfunction "2_2") (pintype "passive"))
      (node (ref "C34") (pin "2") (pinfunction "2_2") (pintype "passive"))
      (node (ref "C35") (pin "2") (pinfunction "2_2") (pintype "passive"))
      (node (ref "C36") (pin "2") (pinfunction "2_2") (pintype "passive"))
      (node (ref "C37") (pin "2") (pinfunction "2_2") (pintype "passive"))
      (node (ref "C38") (pin "2") (pinfunction "2_2") (pintype "passive"))
      (node (ref "C39") (pin "2") (pinfunction "2_2") (pintype "passive"))
      (node (ref "C4") (pin "2") (pinfunction "2_2") (pintype "passive"))
      (node (ref "C40") (pin "2") (pinfunction "2_2") (pintype "passive"))
      (node (ref "C41") (pin "2") (pinfunction "2_2") (pintype "passive"))
      (node (ref "C42") (pin "2") (pinfunction "2_2") (pintype "passive"))
      (node (ref "C43") (pin "2") (pinfunction "2_2") (pintype "passive"))
      (node (ref "C44") (pin "2") (pinfunction "2_2") (pintype "passive"))
      (node (ref "C45") (pin "2") (pinfunction "2_2") (pintype "passive"))
      (node (ref "C46") (pin "2") (pinfunction "2_2") (pintype "passive"))
      (node (ref "C47") (pin "2") (pinfunction "2_2") (pintype "passive"))
      (node (ref "C48") (pin "2") (pinfunction "2_2") (pintype "passive"))
      (node (ref "C49") (pin "2") (pinfunction "2_2") (pintype "passive"))
      (node (ref "C5") (pin "2") (pinfunction "2_2") (pintype "passive"))
      (node (ref "C50") (pin "2") (pinfunction "2_2") (pintype "passive"))
      (node (ref "C51") (pin "2") (pinfunction "2_2") (pintype "passive"))
      (node (ref "C52") (pin "2") (pinfunction "2_2") (pintype "passive"))
      (node (ref "C53") (pin "2") (pinfunction "2_2") (pintype "passive"))
      (node (ref "C54") (pin "2") (pinfunction "2_2") (pintype "passive"))
      (node (ref "C55") (pin "2") (pinfunction "2_2") (pintype "passive"))
      (node (ref "C56") (pin "2") (pinfunction "2_2") (pintype "passive"))
      (node (ref "C57") (pin "2") (pinfunction "2_2") (pintype "passive"))
      (node (ref "C58") (pin "2") (pinfunction "2_2") (pintype "passive"))
      (node (ref "C59") (pin "2") (pinfunction "2_2") (pintype "passive"))
      (node (ref "C6") (pin "2") (pinfunction "2_2") (pintype "passive"))
      (node (ref "C60") (pin "2") (pinfunction "2_2") (pintype "passive"))
      (node (ref "C61") (pin "2") (pinfunction "2_2") (pintype "passive"))
      (node (ref "C62") (pin "2") (pinfunction "2_2") (pintype "passive"))
      (node (ref "C63") (pin "2") (pinfunction "2_2") (pintype "passive"))
      (node (ref "C64") (pin "2") (pinfunction "2_2") (pintype "passive"))
      (node (ref "C65") (pin "2") (pinfunction "2_2") (pintype "passive"))
      (node (ref "C66") (pin "2") (pinfunction "2_2") (pintype "passive"))
      (node (ref "C67") (pin "2") (pinfunction "2_2") (pintype "passive"))
      (node (ref "C68") (pin "2") (pinfunction "2_2") (pintype "passive"))
      (node (ref "C69") (pin "2") (pinfunction "2_2") (pintype "passive"))
      (node (ref "C7") (pin "2") (pinfunction "2_2") (pintype "passive"))
      (node (ref "C70") (pin "2") (pinfunction "2_2") (pintype "passive"))
      (node (ref "C71") (pin "2") (pinfunction "2_2") (pintype "passive"))
      (node (ref "C72") (pin "2") (pinfunction "2_2") (pintype "passive"))
      (node (ref "C73") (pin "2") (pinfunction "2_2") (pintype "passive"))
      (node (ref "C74") (pin "2") (pinfunction "2_2") (pintype "passive"))
      (node (ref "C75") (pin "2") (pinfunction "2_2") (pintype "passive"))
      (node (ref "C76") (pin "2") (pinfunction "2_2") (pintype "passive"))
      (node (ref "C77") (pin "2") (pinfunction "2_2") (pintype "passive"))
      (node (ref "C78") (pin "2") (pinfunction "2_2") (pintype "passive"))
      (node (ref "C79") (pin "2") (pinfunction "2_2") (pintype "passive"))
      (node (ref "C8") (pin "2") (pinfunction "2_2") (pintype "passive"))
      (node (ref "C80") (pin "2") (pinfunction "2_2") (pintype "passive"))
      (node (ref "C81") (pin "2") (pinfunction "2_2") (pintype "passive"))
      (node (ref "C82") (pin "2") (pinfunction "2_2") (pintype "passive"))
      (node (ref "C83") (pin "2") (pinfunction "2_2") (pintype "passive"))
      (node (ref "C84") (pin "2") (pinfunction "2_2") (pintype "passive"))
      (node (ref "C85") (pin "2") (pinfunction "2_2") (pintype "passive"))
      (node (ref "C86") (pin "2") (pinfunction "2_2") (pintype "passive"))
      (node (ref "C87") (pin "2") (pinfunction "2_2") (pintype "passive"))
      (node (ref "C88") (pin "2") (pinfunction "2_2") (pintype "passive"))
      (node (ref "C89") (pin "2") (pinfunction "2_2") (pintype "passive"))
      (node (ref "C9") (pin "2") (pinfunction "2_2") (pintype "passive"))
      (node (ref "DD1") (pin "A12") (pinfunction "GND_A12") (pintype "passive"))
      (node (ref "DD1") (pin "A15") (pinfunction "GND_A15") (pintype "passive"))
      (node (ref "DD1") (pin "A2") (pinfunction "GND_A2") (pintype "passive"))
      (node (ref "DD1") (pin "A25") (pinfunction "GND_A25") (pintype "passive"))
      (node (ref "DD1") (pin "AA21") (pinfunction "GND_PLL1_AA21") (pintype "passive"))
      (node (ref "DD1") (pin "AB11") (pinfunction "GND_AB11") (pintype "passive"))
      (node (ref "DD1") (pin "AB16") (pinfunction "GND_AB16") (pintype "passive"))
      (node (ref "DD1") (pin "AB19") (pinfunction "GND_AB19") (pintype "passive"))
      (node (ref "DD1") (pin "AB7") (pinfunction "GND_AB7") (pintype "passive"))
      (node (ref "DD1") (pin "AC4") (pinfunction "GND_AC4") (pintype "passive"))
      (node (ref "DD1") (pin "AD14") (pinfunction "GND_AD14") (pintype "passive"))
      (node (ref "DD1") (pin "AD18") (pinfunction "GND_AD18") (pintype "passive"))
      (node (ref "DD1") (pin "AD9") (pinfunction "GND_AD9") (pintype "passive"))
      (node (ref "DD1") (pin "AE1") (pinfunction "GND_AE1") (pintype "passive"))
      (node (ref "DD1") (pin "AE26") (pinfunction "GND_AE26") (pintype "passive"))
      (node (ref "DD1") (pin "AF12") (pinfunction "GND_AF12") (pintype "passive"))
      (node (ref "DD1") (pin "AF15") (pinfunction "GND_AF15") (pintype "passive"))
      (node (ref "DD1") (pin "AF2") (pinfunction "GND_AF2") (pintype "passive"))
      (node (ref "DD1") (pin "AF25") (pinfunction "GND_AF25") (pintype "passive"))
      (node (ref "DD1") (pin "B1") (pinfunction "GND_B1") (pintype "passive"))
      (node (ref "DD1") (pin "B26") (pinfunction "GND_B26") (pintype "passive"))
      (node (ref "DD1") (pin "C14") (pinfunction "GND_C14") (pintype "passive"))
      (node (ref "DD1") (pin "C18") (pinfunction "GND_C18") (pintype "passive"))
      (node (ref "DD1") (pin "D24") (pinfunction "GND_D24") (pintype "passive"))
      (node (ref "DD1") (pin "D4") (pinfunction "GND_D4") (pintype "passive"))
      (node (ref "DD1") (pin "E11") (pinfunction "GND_E11") (pintype "passive"))
      (node (ref "DD1") (pin "E16") (pinfunction "GND_E16") (pintype "passive"))
      (node (ref "DD1") (pin "E19") (pinfunction "GND_E19") (pintype "passive"))
      (node (ref "DD1") (pin "E21") (pinfunction "GND_PLL1_E21") (pintype "passive"))
      (node (ref "DD1") (pin "E4") (pinfunction "GND_PLL1_E4") (pintype "passive"))
      (node (ref "DD1") (pin "E7") (pinfunction "GND_E7") (pintype "passive"))
      (node (ref "DD1") (pin "F19") (pinfunction "GND_PLL1_F19") (pintype "passive"))
      (node (ref "DD1") (pin "F8") (pinfunction "GND_PLL1_F8") (pintype "passive"))
      (node (ref "DD1") (pin "G20") (pinfunction "GND_PLL1_G20") (pintype "passive"))
      (node (ref "DD1") (pin "G7") (pinfunction "GND_PLL1_G7") (pintype "passive"))
      (node (ref "DD1") (pin "H13") (pinfunction "GND_H13") (pintype "passive"))
      (node (ref "DD1") (pin "H14") (pinfunction "GND_H14") (pintype "passive"))
      (node (ref "DD1") (pin "H22") (pinfunction "GND_H22") (pintype "passive"))
      (node (ref "DD1") (pin "H5") (pinfunction "GND_H5") (pintype "passive"))
      (node (ref "DD1") (pin "K20") (pinfunction "GND_K20") (pintype "passive"))
      (node (ref "DD1") (pin "L12") (pinfunction "GND_L12") (pintype "passive"))
      (node (ref "DD1") (pin "L13") (pinfunction "GND_L13") (pintype "passive"))
      (node (ref "DD1") (pin "L14") (pinfunction "GND_L14") (pintype "passive"))
      (node (ref "DD1") (pin "L15") (pinfunction "GND_L15") (pintype "passive"))
      (node (ref "DD1") (pin "L22") (pinfunction "GND_L22") (pintype "passive"))
      (node (ref "DD1") (pin "L5") (pinfunction "GND_L5") (pintype "passive"))
      (node (ref "DD1") (pin "M1") (pinfunction "GND_M1") (pintype "passive"))
      (node (ref "DD1") (pin "M12") (pinfunction "GND_M12") (pintype "passive"))
      (node (ref "DD1") (pin "M13") (pinfunction "GND_M13") (pintype "passive"))
      (node (ref "DD1") (pin "M14") (pinfunction "GND_M14") (pintype "passive"))
      (node (ref "DD1") (pin "M15") (pinfunction "GND_M15") (pintype "passive"))
      (node (ref "DD1") (pin "M26") (pinfunction "GND_M26") (pintype "passive"))
      (node (ref "DD1") (pin "N11") (pinfunction "GND_N11") (pintype "passive"))
      (node (ref "DD1") (pin "N12") (pinfunction "GND_N12") (pintype "passive"))
      (node (ref "DD1") (pin "N13") (pinfunction "GND_N13") (pintype "passive"))
      (node (ref "DD1") (pin "N14") (pinfunction "GND_N14") (pintype "passive"))
      (node (ref "DD1") (pin "N15") (pinfunction "GND_N15") (pintype "passive"))
      (node (ref "DD1") (pin "N16") (pinfunction "GND_N16") (pintype "passive"))
      (node (ref "DD1") (pin "N19") (pinfunction "GND_N19") (pintype "passive"))
      (node (ref "DD1") (pin "N8") (pinfunction "GND_N8") (pintype "passive"))
      (node (ref "DD1") (pin "P11") (pinfunction "GND_P11") (pintype "passive"))
      (node (ref "DD1") (pin "P12") (pinfunction "GND_P12") (pintype "passive"))
      (node (ref "DD1") (pin "P13") (pinfunction "GND_P13") (pintype "passive"))
      (node (ref "DD1") (pin "P14") (pinfunction "GND_P14") (pintype "passive"))
      (node (ref "DD1") (pin "P15") (pinfunction "GND_P15") (pintype "passive"))
      (node (ref "DD1") (pin "P16") (pinfunction "GND_P16") (pintype "passive"))
      (node (ref "DD1") (pin "P19") (pinfunction "GND_P19") (pintype "passive"))
      (node (ref "DD1") (pin "P8") (pinfunction "GND_P8") (pintype "passive"))
      (node (ref "DD1") (pin "R1") (pinfunction "GND_R1") (pintype "passive"))
      (node (ref "DD1") (pin "R12") (pinfunction "GND_R12") (pintype "passive"))
      (node (ref "DD1") (pin "R13") (pinfunction "GND_R13") (pintype "passive"))
      (node (ref "DD1") (pin "R14") (pinfunction "GND_R14") (pintype "passive"))
      (node (ref "DD1") (pin "R15") (pinfunction "GND_R15") (pintype "passive"))
      (node (ref "DD1") (pin "R21") (pinfunction "GND_R21") (pintype "passive"))
      (node (ref "DD1") (pin "R26") (pinfunction "GND_R26") (pintype "passive"))
      (node (ref "DD1") (pin "T12") (pinfunction "GND_T12") (pintype "passive"))
      (node (ref "DD1") (pin "T13") (pinfunction "GND_T13") (pintype "passive"))
      (node (ref "DD1") (pin "T14") (pinfunction "GND_T14") (pintype "passive"))
      (node (ref "DD1") (pin "T15") (pinfunction "GND_T15") (pintype "passive"))
      (node (ref "DD1") (pin "T5") (pinfunction "GND_T5") (pintype "passive"))
      (node (ref "DD1") (pin "U19") (pinfunction "GND_U19") (pintype "passive"))
      (node (ref "DD1") (pin "U8") (pinfunction "GND_U8") (pintype "passive"))
      (node (ref "DD1") (pin "W13") (pinfunction "GND_W13") (pintype "passive"))
      (node (ref "DD1") (pin "W14") (pinfunction "GND_W14") (pintype "passive"))
      (node (ref "DD1") (pin "W20") (pinfunction "GND_PLL1_W20") (pintype "passive"))
      (node (ref "DD1") (pin "W22") (pinfunction "GND_W22") (pintype "passive"))
      (node (ref "DD1") (pin "W5") (pinfunction "GND_W5") (pintype "passive"))
      (node (ref "DD1") (pin "W7") (pinfunction "GND_PLL1_W7") (pintype "passive"))
      (node (ref "DD1") (pin "Y17") (pinfunction "GND_Y17") (pintype "passive"))
      (node (ref "DD1") (pin "Y19") (pinfunction "GND_PLL1_Y19") (pintype "passive"))
      (node (ref "DD1") (pin "Y6") (pinfunction "GND_PLL1_Y6") (pintype "passive"))
      (node (ref "DD1") (pin "Y8") (pinfunction "GND_PLL1_Y8") (pintype "passive"))
      (node (ref "DD1") (pin "Y9") (pinfunction "GND_Y9") (pintype "passive"))
    )
    (net (code "43") (name "OVF_ADC_A") (class "Default")
      (node (ref "DD1") (pin "AF7") (pinfunction "LVDS189n_AF7") (pintype "passive"))
    )
    (net (code "44") (name "OVF_ADC_B") (class "Default")
      (node (ref "DD1") (pin "AE19") (pinfunction "LVDS165n_AE19") (pintype "passive"))
    )
    (net (code "45") (name "UART_RXD") (class "Default")
      (node (ref "DD1") (pin "D1") (pinfunction "LVDS45n_D1") (pintype "passive"))
    )
    (net (code "46") (name "UART_TXD") (class "Default")
      (node (ref "DD1") (pin "E1") (pinfunction "LVDS43n_E1") (pintype "passive"))
    )
    (net (code "47") (name "VCC12") (class "Default")
      (node (ref "C1") (pin "1") (pinfunction "1_1") (pintype "passive"))
      (node (ref "C10") (pin "1") (pinfunction "1_1") (pintype "passive"))
      (node (ref "C11") (pin "1") (pinfunction "1_1") (pintype "passive"))
      (node (ref "C12") (pin "1") (pinfunction "1_1") (pintype "passive"))
      (node (ref "C13") (pin "1") (pinfunction "1_1") (pintype "passive"))
      (node (ref "C14") (pin "1") (pinfunction "1_1") (pintype "passive"))
      (node (ref "C15") (pin "1") (pinfunction "1_1") (pintype "passive"))
      (node (ref "C16") (pin "1") (pinfunction "1_1") (pintype "passive"))
      (node (ref "C17") (pin "1") (pinfunction "1_1") (pintype "passive"))
      (node (ref "C18") (pin "1") (pinfunction "1_1") (pintype "passive"))
      (node (ref "C19") (pin "1") (pinfunction "1_1") (pintype "passive"))
      (node (ref "C2") (pin "1") (pinfunction "1_1") (pintype "passive"))
      (node (ref "C20") (pin "1") (pinfunction "1_1") (pintype "passive"))
      (node (ref "C21") (pin "1") (pinfunction "1_1") (pintype "passive"))
      (node (ref "C22") (pin "1") (pinfunction "1_1") (pintype "passive"))
      (node (ref "C23") (pin "1") (pinfunction "1_1") (pintype "passive"))
      (node (ref "C24") (pin "1") (pinfunction "1_1") (pintype "passive"))
      (node (ref "C25") (pin "1") (pinfunction "1_1") (pintype "passive"))
      (node (ref "C26") (pin "1") (pinfunction "1_1") (pintype "passive"))
      (node (ref "C27") (pin "1") (pinfunction "1_1") (pintype "passive"))
      (node (ref "C28") (pin "1") (pinfunction "1_1") (pintype "passive"))
      (node (ref "C29") (pin "1") (pinfunction "1_1") (pintype "passive"))
      (node (ref "C3") (pin "1") (pinfunction "1_1") (pintype "passive"))
      (node (ref "C30") (pin "1") (pinfunction "1_1") (pintype "passive"))
      (node (ref "C31") (pin "1") (pinfunction "1_1") (pintype "passive"))
      (node (ref "C32") (pin "1") (pinfunction "1_1") (pintype "passive"))
      (node (ref "C33") (pin "1") (pinfunction "1_1") (pintype "passive"))
      (node (ref "C34") (pin "1") (pinfunction "1_1") (pintype "passive"))
      (node (ref "C35") (pin "1") (pinfunction "1_1") (pintype "passive"))
      (node (ref "C36") (pin "1") (pinfunction "1_1") (pintype "passive"))
      (node (ref "C4") (pin "1") (pinfunction "1_1") (pintype "passive"))
      (node (ref "C5") (pin "1") (pinfunction "1_1") (pintype "passive"))
      (node (ref "C6") (pin "1") (pinfunction "1_1") (pintype "passive"))
      (node (ref "C7") (pin "1") (pinfunction "1_1") (pintype "passive"))
      (node (ref "C8") (pin "1") (pinfunction "1_1") (pintype "passive"))
      (node (ref "C9") (pin "1") (pinfunction "1_1") (pintype "passive"))
      (node (ref "DD1") (pin "AA19") (pinfunction "VCCA_PLL4_AA19") (pintype "passive"))
      (node (ref "DD1") (pin "AA8") (pinfunction "VCCA_PLL4_AA8") (pintype "passive"))
      (node (ref "DD1") (pin "G19") (pinfunction "VCCA_PLL4_G19") (pintype "passive"))
      (node (ref "DD1") (pin "G8") (pinfunction "VCCA_PLL4_G8") (pintype "passive"))
      (node (ref "DD1") (pin "H20") (pinfunction "VCCA_PLL4_H20") (pintype "passive"))
      (node (ref "DD1") (pin "H7") (pinfunction "VCCA_PLL4_H7") (pintype "passive"))
      (node (ref "DD1") (pin "K10") (pinfunction "VCCINT_K10") (pintype "passive"))
      (node (ref "DD1") (pin "K11") (pinfunction "VCCINT_K11") (pintype "passive"))
      (node (ref "DD1") (pin "K12") (pinfunction "VCCINT_K12") (pintype "passive"))
      (node (ref "DD1") (pin "K13") (pinfunction "VCCINT_K13") (pintype "passive"))
      (node (ref "DD1") (pin "K14") (pinfunction "VCCINT_K14") (pintype "passive"))
      (node (ref "DD1") (pin "K15") (pinfunction "VCCINT_K15") (pintype "passive"))
      (node (ref "DD1") (pin "L11") (pinfunction "VCCINT_L11") (pintype "passive"))
      (node (ref "DD1") (pin "L16") (pinfunction "VCCINT_L16") (pintype "passive"))
      (node (ref "DD1") (pin "L17") (pinfunction "VCCINT_L17") (pintype "passive"))
      (node (ref "DD1") (pin "L18") (pinfunction "VCCINT_L18") (pintype "passive"))
      (node (ref "DD1") (pin "M10") (pinfunction "VCCINT_M10") (pintype "passive"))
      (node (ref "DD1") (pin "M11") (pinfunction "VCCINT_M11") (pintype "passive"))
      (node (ref "DD1") (pin "M16") (pinfunction "VCCINT_M16") (pintype "passive"))
      (node (ref "DD1") (pin "M17") (pinfunction "VCCINT_M17") (pintype "passive"))
      (node (ref "DD1") (pin "N10") (pinfunction "VCCINT_N10") (pintype "passive"))
      (node (ref "DD1") (pin "N17") (pinfunction "VCCINT_N17") (pintype "passive"))
      (node (ref "DD1") (pin "P10") (pinfunction "VCCINT_P10") (pintype "passive"))
      (node (ref "DD1") (pin "R10") (pinfunction "VCCINT_R10") (pintype "passive"))
      (node (ref "DD1") (pin "R11") (pinfunction "VCCINT_R11") (pintype "passive"))
      (node (ref "DD1") (pin "R16") (pinfunction "VCCINT_R16") (pintype "passive"))
      (node (ref "DD1") (pin "T11") (pinfunction "VCCINT_T11") (pintype "passive"))
      (node (ref "DD1") (pin "T16") (pinfunction "VCCINT_T16") (pintype "passive"))
      (node (ref "DD1") (pin "U11") (pinfunction "VCCINT_U11") (pintype "passive"))
      (node (ref "DD1") (pin "U13") (pinfunction "VCCINT_U13") (pintype "passive"))
      (node (ref "DD1") (pin "U14") (pinfunction "VCCINT_U14") (pintype "passive"))
      (node (ref "DD1") (pin "U15") (pinfunction "VCCINT_U15") (pintype "passive"))
      (node (ref "DD1") (pin "U16") (pinfunction "VCCINT_U16") (pintype "passive"))
      (node (ref "DD1") (pin "V16") (pinfunction "VCCINT_V16") (pintype "passive"))
      (node (ref "DD1") (pin "V7") (pinfunction "VCCA_PLL4_V7") (pintype "passive"))
      (node (ref "DD1") (pin "Y20") (pinfunction "VCCA_PLL4_Y20") (pintype "passive"))
    )
    (net (code "48") (name "VCC33") (class "Default")
      (node (ref "C37") (pin "1") (pinfunction "1_1") (pintype "passive"))
      (node (ref "C38") (pin "1") (pinfunction "1_1") (pintype "passive"))
      (node (ref "C39") (pin "1") (pinfunction "1_1") (pintype "passive"))
      (node (ref "C40") (pin "1") (pinfunction "1_1") (pintype "passive"))
      (node (ref "C41") (pin "1") (pinfunction "1_1") (pintype "passive"))
      (node (ref "C42") (pin "1") (pinfunction "1_1") (pintype "passive"))
      (node (ref "C43") (pin "1") (pinfunction "1_1") (pintype "passive"))
      (node (ref "C44") (pin "1") (pinfunction "1_1") (pintype "passive"))
      (node (ref "C45") (pin "1") (pinfunction "1_1") (pintype "passive"))
      (node (ref "C46") (pin "1") (pinfunction "1_1") (pintype "passive"))
      (node (ref "C47") (pin "1") (pinfunction "1_1") (pintype "passive"))
      (node (ref "C48") (pin "1") (pinfunction "1_1") (pintype "passive"))
      (node (ref "C49") (pin "1") (pinfunction "1_1") (pintype "passive"))
      (node (ref "C50") (pin "1") (pinfunction "1_1") (pintype "passive"))
      (node (ref "C51") (pin "1") (pinfunction "1_1") (pintype "passive"))
      (node (ref "C52") (pin "1") (pinfunction "1_1") (pintype "passive"))
      (node (ref "C53") (pin "1") (pinfunction "1_1") (pintype "passive"))
      (node (ref "C54") (pin "1") (pinfunction "1_1") (pintype "passive"))
      (node (ref "C55") (pin "1") (pinfunction "1_1") (pintype "passive"))
      (node (ref "C56") (pin "1") (pinfunction "1_1") (pintype "passive"))
      (node (ref "C57") (pin "1") (pinfunction "1_1") (pintype "passive"))
      (node (ref "C58") (pin "1") (pinfunction "1_1") (pintype "passive"))
      (node (ref "C59") (pin "1") (pinfunction "1_1") (pintype "passive"))
      (node (ref "C60") (pin "1") (pinfunction "1_1") (pintype "passive"))
      (node (ref "C61") (pin "1") (pinfunction "1_1") (pintype "passive"))
      (node (ref "C62") (pin "1") (pinfunction "1_1") (pintype "passive"))
      (node (ref "C63") (pin "1") (pinfunction "1_1") (pintype "passive"))
      (node (ref "C64") (pin "1") (pinfunction "1_1") (pintype "passive"))
      (node (ref "C65") (pin "1") (pinfunction "1_1") (pintype "passive"))
      (node (ref "C66") (pin "1") (pinfunction "1_1") (pintype "passive"))
      (node (ref "C67") (pin "1") (pinfunction "1_1") (pintype "passive"))
      (node (ref "C68") (pin "1") (pinfunction "1_1") (pintype "passive"))
      (node (ref "C69") (pin "1") (pinfunction "1_1") (pintype "passive"))
      (node (ref "C70") (pin "1") (pinfunction "1_1") (pintype "passive"))
      (node (ref "C71") (pin "1") (pinfunction "1_1") (pintype "passive"))
      (node (ref "C72") (pin "1") (pinfunction "1_1") (pintype "passive"))
      (node (ref "C73") (pin "1") (pinfunction "1_1") (pintype "passive"))
      (node (ref "C74") (pin "1") (pinfunction "1_1") (pintype "passive"))
      (node (ref "C75") (pin "1") (pinfunction "1_1") (pintype "passive"))
      (node (ref "C76") (pin "1") (pinfunction "1_1") (pintype "passive"))
      (node (ref "C77") (pin "1") (pinfunction "1_1") (pintype "passive"))
      (node (ref "C78") (pin "1") (pinfunction "1_1") (pintype "passive"))
      (node (ref "C79") (pin "1") (pinfunction "1_1") (pintype "passive"))
      (node (ref "C80") (pin "1") (pinfunction "1_1") (pintype "passive"))
      (node (ref "C81") (pin "1") (pinfunction "1_1") (pintype "passive"))
      (node (ref "C82") (pin "1") (pinfunction "1_1") (pintype "passive"))
      (node (ref "C83") (pin "1") (pinfunction "1_1") (pintype "passive"))
      (node (ref "C84") (pin "1") (pinfunction "1_1") (pintype "passive"))
      (node (ref "C85") (pin "1") (pinfunction "1_1") (pintype "passive"))
      (node (ref "C86") (pin "1") (pinfunction "1_1") (pintype "passive"))
      (node (ref "C87") (pin "1") (pinfunction "1_1") (pintype "passive"))
      (node (ref "C88") (pin "1") (pinfunction "1_1") (pintype "passive"))
      (node (ref "C89") (pin "1") (pinfunction "1_1") (pintype "passive"))
      (node (ref "DD1") (pin "A11") (pinfunction "VCCIO1_A11") (pintype "passive"))
      (node (ref "DD1") (pin "A16") (pinfunction "VCCIO1_A16") (pintype "passive"))
      (node (ref "DD1") (pin "A24") (pinfunction "VCCIO1_A24") (pintype "passive"))
      (node (ref "DD1") (pin "A3") (pinfunction "VCCIO1_A3") (pintype "passive"))
      (node (ref "DD1") (pin "AA22") (pinfunction "VCCIO1_AA22") (pintype "passive"))
      (node (ref "DD1") (pin "AB13") (pinfunction "VCCIO1_AB13") (pintype "passive"))
      (node (ref "DD1") (pin "AB14") (pinfunction "VCCIO1_AB14") (pintype "passive"))
      (node (ref "DD1") (pin "AB17") (pinfunction "VCCIO1_AB17") (pintype "passive"))
      (node (ref "DD1") (pin "AB22") (pinfunction "VCCIO1_AB22") (pintype "passive"))
      (node (ref "DD1") (pin "AB5") (pinfunction "VCCIO1_AB5") (pintype "passive"))
      (node (ref "DD1") (pin "AB6") (pinfunction "VCCIO1_AB6") (pintype "passive"))
      (node (ref "DD1") (pin "AB9") (pinfunction "VCCIO1_AB9") (pintype "passive"))
      (node (ref "DD1") (pin "AD1") (pinfunction "VCCIO1_AD1") (pintype "passive"))
      (node (ref "DD1") (pin "AD20") (pinfunction "VCCIO1_AD20") (pintype "passive"))
      (node (ref "DD1") (pin "AD26") (pinfunction "VCCIO1_AD26") (pintype "passive"))
      (node (ref "DD1") (pin "AF11") (pinfunction "VCCIO1_AF11") (pintype "passive"))
      (node (ref "DD1") (pin "AF16") (pinfunction "VCCIO1_AF16") (pintype "passive"))
      (node (ref "DD1") (pin "AF24") (pinfunction "VCCIO1_AF24") (pintype "passive"))
      (node (ref "DD1") (pin "AF3") (pinfunction "VCCIO1_AF3") (pintype "passive"))
      (node (ref "DD1") (pin "C1") (pinfunction "VCCIO1_C1") (pintype "passive"))
      (node (ref "DD1") (pin "C20") (pinfunction "VCCIO1_C20") (pintype "passive"))
      (node (ref "DD1") (pin "C26") (pinfunction "VCCIO1_C26") (pintype "passive"))
      (node (ref "DD1") (pin "E13") (pinfunction "VCCIO1_E13") (pintype "passive"))
      (node (ref "DD1") (pin "E14") (pinfunction "VCCIO1_E14") (pintype "passive"))
      (node (ref "DD1") (pin "E17") (pinfunction "VCCIO1_E17") (pintype "passive"))
      (node (ref "DD1") (pin "E6") (pinfunction "VCCIO1_E6") (pintype "passive"))
      (node (ref "DD1") (pin "E9") (pinfunction "VCCIO1_E9") (pintype "passive"))
      (node (ref "DD1") (pin "F22") (pinfunction "VCCIO1_F22") (pintype "passive"))
      (node (ref "DD1") (pin "F5") (pinfunction "VCCIO1_F5") (pintype "passive"))
      (node (ref "DD1") (pin "H18") (pinfunction "VCCIO1_H18") (pintype "passive"))
      (node (ref "DD1") (pin "H9") (pinfunction "VCCIO1_H9") (pintype "passive"))
      (node (ref "DD1") (pin "J12") (pinfunction "VCCIO1_J12") (pintype "passive"))
      (node (ref "DD1") (pin "J15") (pinfunction "VCCIO1_J15") (pintype "passive"))
      (node (ref "DD1") (pin "J19") (pinfunction "VCCIO1_J19") (pintype "passive"))
      (node (ref "DD1") (pin "L1") (pinfunction "VCCIO1_L1") (pintype "passive"))
      (node (ref "DD1") (pin "L26") (pinfunction "VCCIO1_L26") (pintype "passive"))
      (node (ref "DD1") (pin "M18") (pinfunction "VCCIO1_M18") (pintype "passive"))
      (node (ref "DD1") (pin "M9") (pinfunction "VCCIO1_M9") (pintype "passive"))
      (node (ref "DD1") (pin "N22") (pinfunction "VCCIO1_N22") (pintype "passive"))
      (node (ref "DD1") (pin "N5") (pinfunction "VCCIO1_N5") (pintype "passive"))
      (node (ref "DD1") (pin "O22") (pinfunction "VCCIO1_O22") (pintype "passive"))
      (node (ref "DD1") (pin "P22") (pinfunction "VCCIO1_P22") (pintype "passive"))
      (node (ref "DD1") (pin "P5") (pinfunction "VCCIO1_P5") (pintype "passive"))
      (node (ref "DD1") (pin "R18") (pinfunction "VCCIO1_R18") (pintype "passive"))
      (node (ref "DD1") (pin "R9") (pinfunction "VCCIO1_R9") (pintype "passive"))
      (node (ref "DD1") (pin "T1") (pinfunction "VCCIO1_T1") (pintype "passive"))
      (node (ref "DD1") (pin "T26") (pinfunction "VCCIO1_T26") (pintype "passive"))
      (node (ref "DD1") (pin "V12") (pinfunction "VCCIO1_V12") (pintype "passive"))
      (node (ref "DD1") (pin "V15") (pinfunction "VCCIO1_V15") (pintype "passive"))
      (node (ref "DD1") (pin "V19") (pinfunction "VCCIO1_V19") (pintype "passive"))
      (node (ref "DD1") (pin "V8") (pinfunction "VCCIO1_V8") (pintype "passive"))
      (node (ref "DD1") (pin "W18") (pinfunction "VCCIO1_W18") (pintype "passive"))
      (node (ref "DD1") (pin "W9") (pinfunction "VCCIO1_W9") (pintype "passive"))
    )
    (net (code "49") (name "unconnected-(DD1B-LVDS50n-PadC5)") (class "Default")
      (node (ref "DD1") (pin "C5") (pinfunction "LVDS50n_C5") (pintype "passive"))
    )
    (net (code "50") (name "unconnected-(DD1B-LVDS50p-PadC6)") (class "Default")
      (node (ref "DD1") (pin "C6") (pinfunction "LVDS50p_C6") (pintype "passive"))
    )
    (net (code "51") (name "unconnected-(DD1B-LVDS51n-PadB4)") (class "Default")
      (node (ref "DD1") (pin "B4") (pinfunction "LVDS51n_B4") (pintype "passive"))
    )
    (net (code "52") (name "unconnected-(DD1B-LVDS51p-PadA4)") (class "Default")
      (node (ref "DD1") (pin "A4") (pinfunction "LVDS51p_A4") (pintype "passive"))
    )
    (net (code "53") (name "unconnected-(DD1B-LVDS52n-PadB5)") (class "Default")
      (node (ref "DD1") (pin "B5") (pinfunction "LVDS52n_B5") (pintype "passive"))
    )
    (net (code "54") (name "unconnected-(DD1B-LVDS52p-PadA5)") (class "Default")
      (node (ref "DD1") (pin "A5") (pinfunction "LVDS52p_A5") (pintype "passive"))
    )
    (net (code "55") (name "unconnected-(DD1B-LVDS53n-PadA6)") (class "Default")
      (node (ref "DD1") (pin "A6") (pinfunction "LVDS53n_A6") (pintype "passive"))
    )
    (net (code "56") (name "unconnected-(DD1B-LVDS53p-PadB6)") (class "Default")
      (node (ref "DD1") (pin "B6") (pinfunction "LVDS53p_B6") (pintype "passive"))
    )
    (net (code "57") (name "unconnected-(DD1B-LVDS54n-PadD5)") (class "Default")
      (node (ref "DD1") (pin "D5") (pinfunction "LVDS54n_D5") (pintype "passive"))
    )
    (net (code "58") (name "unconnected-(DD1B-LVDS54p-PadC4)") (class "Default")
      (node (ref "DD1") (pin "C4") (pinfunction "LVDS54p_C4") (pintype "passive"))
    )
    (net (code "59") (name "unconnected-(DD1B-LVDS56n-PadG9)") (class "Default")
      (node (ref "DD1") (pin "G9") (pinfunction "LVDS56n_G9") (pintype "passive"))
    )
    (net (code "60") (name "unconnected-(DD1B-LVDS56p-PadH10)") (class "Default")
      (node (ref "DD1") (pin "H10") (pinfunction "LVDS56p_H10") (pintype "passive"))
    )
    (net (code "61") (name "unconnected-(DD1B-LVDS57n-PadC7)") (class "Default")
      (node (ref "DD1") (pin "C7") (pinfunction "LVDS57n_C7") (pintype "passive"))
    )
    (net (code "62") (name "unconnected-(DD1B-LVDS57p-PadD7)") (class "Default")
      (node (ref "DD1") (pin "D7") (pinfunction "LVDS57p_D7") (pintype "passive"))
    )
    (net (code "63") (name "unconnected-(DD1B-LVDS58n-PadA7)") (class "Default")
      (node (ref "DD1") (pin "A7") (pinfunction "LVDS58n_A7") (pintype "passive"))
    )
    (net (code "64") (name "unconnected-(DD1B-LVDS58p-PadB7)") (class "Default")
      (node (ref "DD1") (pin "B7") (pinfunction "LVDS58p_B7") (pintype "passive"))
    )
    (net (code "65") (name "unconnected-(DD1B-LVDS59n-PadC8)") (class "Default")
      (node (ref "DD1") (pin "C8") (pinfunction "LVDS59n_C8") (pintype "passive"))
    )
    (net (code "66") (name "unconnected-(DD1B-LVDS59p-PadD8)") (class "Default")
      (node (ref "DD1") (pin "D8") (pinfunction "LVDS59p_D8") (pintype "passive"))
    )
    (net (code "67") (name "unconnected-(DD1B-LVDS60n-PadG10)") (class "Default")
      (node (ref "DD1") (pin "G10") (pinfunction "LVDS60n_G10") (pintype "passive"))
    )
    (net (code "68") (name "unconnected-(DD1B-LVDS60p-PadF10)") (class "Default")
      (node (ref "DD1") (pin "F10") (pinfunction "LVDS60p_F10") (pintype "passive"))
    )
    (net (code "69") (name "unconnected-(DD1B-LVDS61n-PadC9)") (class "Default")
      (node (ref "DD1") (pin "C9") (pinfunction "LVDS61n_C9") (pintype "passive"))
    )
    (net (code "70") (name "unconnected-(DD1B-LVDS61p-PadD9)") (class "Default")
      (node (ref "DD1") (pin "D9") (pinfunction "LVDS61p_D9") (pintype "passive"))
    )
    (net (code "71") (name "unconnected-(DD1B-LVDS62n-PadA8)") (class "Default")
      (node (ref "DD1") (pin "A8") (pinfunction "LVDS62n_A8") (pintype "passive"))
    )
    (net (code "72") (name "unconnected-(DD1B-LVDS62p-PadB8)") (class "Default")
      (node (ref "DD1") (pin "B8") (pinfunction "LVDS62p_B8") (pintype "passive"))
    )
    (net (code "73") (name "unconnected-(DD1B-LVDS63n-PadH12)") (class "Default")
      (node (ref "DD1") (pin "H12") (pinfunction "LVDS63n_H12") (pintype "passive"))
    )
    (net (code "74") (name "unconnected-(DD1B-LVDS63p-PadH11)") (class "Default")
      (node (ref "DD1") (pin "H11") (pinfunction "LVDS63p_H11") (pintype "passive"))
    )
    (net (code "75") (name "unconnected-(DD1C-IO3_0-PadD6)") (class "Default")
      (node (ref "DD1") (pin "D6") (pinfunction "IO3_0_D6") (pintype "passive"))
    )
    (net (code "76") (name "unconnected-(DD1C-IO3_1-PadF9)") (class "Default")
      (node (ref "DD1") (pin "F9") (pinfunction "IO3_1_F9") (pintype "passive"))
    )
    (net (code "77") (name "unconnected-(DD1C-IO3_2-PadG11)") (class "Default")
      (node (ref "DD1") (pin "G11") (pinfunction "IO3_2_G11") (pintype "passive"))
    )
    (net (code "78") (name "unconnected-(DD1C-IO3_3-PadH8)") (class "Default")
      (node (ref "DD1") (pin "H8") (pinfunction "IO3_3_H8") (pintype "passive"))
    )
    (net (code "79") (name "unconnected-(DD1C-LVDS55n-PadJ9)") (class "Default")
      (node (ref "DD1") (pin "J9") (pinfunction "LVDS55n_J9") (pintype "passive"))
    )
    (net (code "80") (name "unconnected-(DD1C-LVDS55p-PadK9)") (class "Default")
      (node (ref "DD1") (pin "K9") (pinfunction "LVDS55p_K9") (pintype "passive"))
    )
    (net (code "81") (name "unconnected-(DD1C-LVDS64n-PadE10)") (class "Default")
      (node (ref "DD1") (pin "E10") (pinfunction "LVDS64n_E10") (pintype "passive"))
    )
    (net (code "82") (name "unconnected-(DD1C-LVDS64p-PadF11)") (class "Default")
      (node (ref "DD1") (pin "F11") (pinfunction "LVDS64p_F11") (pintype "passive"))
    )
    (net (code "83") (name "unconnected-(DD1C-LVDS65n-PadA9)") (class "Default")
      (node (ref "DD1") (pin "A9") (pinfunction "LVDS65n_A9") (pintype "passive"))
    )
    (net (code "84") (name "unconnected-(DD1C-LVDS65p-PadB9)") (class "Default")
      (node (ref "DD1") (pin "B9") (pinfunction "LVDS65p_B9") (pintype "passive"))
    )
    (net (code "85") (name "unconnected-(DD1C-LVDS66n-PadD10)") (class "Default")
      (node (ref "DD1") (pin "D10") (pinfunction "LVDS66n_D10") (pintype "passive"))
    )
    (net (code "86") (name "unconnected-(DD1C-LVDS66p-PadC10)") (class "Default")
      (node (ref "DD1") (pin "C10") (pinfunction "LVDS66p_C10") (pintype "passive"))
    )
    (net (code "87") (name "unconnected-(DD1C-LVDS67n-PadA10)") (class "Default")
      (node (ref "DD1") (pin "A10") (pinfunction "LVDS67n_A10") (pintype "passive"))
    )
    (net (code "88") (name "unconnected-(DD1C-LVDS67p-PadB10)") (class "Default")
      (node (ref "DD1") (pin "B10") (pinfunction "LVDS67p_B10") (pintype "passive"))
    )
    (net (code "89") (name "unconnected-(DD1C-LVDS68n-PadD12)") (class "Default")
      (node (ref "DD1") (pin "D12") (pinfunction "LVDS68n_D12") (pintype "passive"))
    )
    (net (code "90") (name "unconnected-(DD1C-LVDS68p-PadE12)") (class "Default")
      (node (ref "DD1") (pin "E12") (pinfunction "LVDS68p_E12") (pintype "passive"))
    )
    (net (code "91") (name "unconnected-(DD1C-LVDS69n-PadJ14)") (class "Default")
      (node (ref "DD1") (pin "J14") (pinfunction "LVDS69n_J14") (pintype "passive"))
    )
    (net (code "92") (name "unconnected-(DD1C-LVDS69p-PadJ13)") (class "Default")
      (node (ref "DD1") (pin "J13") (pinfunction "LVDS69p_J13") (pintype "passive"))
    )
    (net (code "93") (name "unconnected-(DD1C-LVDS70n-PadG12)") (class "Default")
      (node (ref "DD1") (pin "G12") (pinfunction "LVDS70n_G12") (pintype "passive"))
    )
    (net (code "94") (name "unconnected-(DD1C-LVDS70p-PadF12)") (class "Default")
      (node (ref "DD1") (pin "F12") (pinfunction "LVDS70p_F12") (pintype "passive"))
    )
    (net (code "95") (name "unconnected-(DD1C-LVDS71n-PadJ11)") (class "Default")
      (node (ref "DD1") (pin "J11") (pinfunction "LVDS71n_J11") (pintype "passive"))
    )
    (net (code "96") (name "unconnected-(DD1C-LVDS71p-PadJ10)") (class "Default")
      (node (ref "DD1") (pin "J10") (pinfunction "LVDS71p_J10") (pintype "passive"))
    )
    (net (code "97") (name "unconnected-(DD1C-LVDS72n-PadB11)") (class "Default")
      (node (ref "DD1") (pin "B11") (pinfunction "LVDS72n_B11") (pintype "passive"))
    )
    (net (code "98") (name "unconnected-(DD1C-LVDS72p-PadC11)") (class "Default")
      (node (ref "DD1") (pin "C11") (pinfunction "LVDS72p_C11") (pintype "passive"))
    )
    (net (code "99") (name "unconnected-(DD1C-LVDS73n-PadB12)") (class "Default")
      (node (ref "DD1") (pin "B12") (pinfunction "LVDS73n_B12") (pintype "passive"))
    )
    (net (code "100") (name "unconnected-(DD1C-LVDS73p-PadC12)") (class "Default")
      (node (ref "DD1") (pin "C12") (pinfunction "LVDS73p_C12") (pintype "passive"))
    )
    (net (code "101") (name "unconnected-(DD1C-LVDSCLK5n-PadC13)") (class "Default")
      (node (ref "DD1") (pin "C13") (pinfunction "LVDSCLK5n_C13") (pintype "passive"))
    )
    (net (code "102") (name "unconnected-(DD1C-LVDSCLK5p-PadD13)") (class "Default")
      (node (ref "DD1") (pin "D13") (pinfunction "LVDSCLK5p_D13") (pintype "passive"))
    )
    (net (code "103") (name "unconnected-(DD1C-VREFB3N0-PadD11)") (class "Default")
      (node (ref "DD1") (pin "D11") (pinfunction "VREFB3N0_D11") (pintype "passive"))
    )
    (net (code "104") (name "unconnected-(DD1C-VREFB3N1-PadE8)") (class "Default")
      (node (ref "DD1") (pin "E8") (pinfunction "VREFB3N1_E8") (pintype "passive"))
    )
    (net (code "105") (name "unconnected-(DD1D-LVDS74n-PadA14)") (class "Default")
      (node (ref "DD1") (pin "A14") (pinfunction "LVDS74n_A14") (pintype "passive"))
    )
    (net (code "106") (name "unconnected-(DD1D-LVDS74p-PadB14)") (class "Default")
      (node (ref "DD1") (pin "B14") (pinfunction "LVDS74p_B14") (pintype "passive"))
    )
    (net (code "107") (name "unconnected-(DD1D-LVDS75n-PadG14)") (class "Default")
      (node (ref "DD1") (pin "G14") (pinfunction "LVDS75n_G14") (pintype "passive"))
    )
    (net (code "108") (name "unconnected-(DD1D-LVDS75p-PadF14)") (class "Default")
      (node (ref "DD1") (pin "F14") (pinfunction "LVDS75p_F14") (pintype "passive"))
    )
    (net (code "109") (name "unconnected-(DD1D-LVDS76n-PadG13)") (class "Default")
      (node (ref "DD1") (pin "G13") (pinfunction "LVDS76n_G13") (pintype "passive"))
    )
    (net (code "110") (name "unconnected-(DD1D-LVDS76p-PadF13)") (class "Default")
      (node (ref "DD1") (pin "F13") (pinfunction "LVDS76p_F13") (pintype "passive"))
    )
    (net (code "111") (name "unconnected-(DD1D-LVDS77n-PadB15)") (class "Default")
      (node (ref "DD1") (pin "B15") (pinfunction "LVDS77n_B15") (pintype "passive"))
    )
    (net (code "112") (name "unconnected-(DD1D-LVDS77p-PadС15)") (class "Default")
      (node (ref "DD1") (pin "С15") (pinfunction "LVDS77p_С15") (pintype "passive"))
    )
    (net (code "113") (name "unconnected-(DD1D-LVDS78n-PadC16)") (class "Default")
      (node (ref "DD1") (pin "C16") (pinfunction "LVDS78n_C16") (pintype "passive"))
    )
    (net (code "114") (name "unconnected-(DD1D-LVDS78p-PadB16)") (class "Default")
      (node (ref "DD1") (pin "B16") (pinfunction "LVDS78p_B16") (pintype "passive"))
    )
    (net (code "115") (name "unconnected-(DD1D-LVDS80n-PadH16)") (class "Default")
      (node (ref "DD1") (pin "H16") (pinfunction "LVDS80n_H16") (pintype "passive"))
    )
    (net (code "116") (name "unconnected-(DD1D-LVDS80p-PadH15)") (class "Default")
      (node (ref "DD1") (pin "H15") (pinfunction "LVDS80p_H15") (pintype "passive"))
    )
    (net (code "117") (name "unconnected-(DD1D-LVDS81n-PadB17)") (class "Default")
      (node (ref "DD1") (pin "B17") (pinfunction "LVDS81n_B17") (pintype "passive"))
    )
    (net (code "118") (name "unconnected-(DD1D-LVDS81p-PadA17)") (class "Default")
      (node (ref "DD1") (pin "A17") (pinfunction "LVDS81p_A17") (pintype "passive"))
    )
    (net (code "119") (name "unconnected-(DD1D-LVDS82n-PadF15)") (class "Default")
      (node (ref "DD1") (pin "F15") (pinfunction "LVDS82n_F15") (pintype "passive"))
    )
    (net (code "120") (name "unconnected-(DD1D-LVDS82p-PadG15)") (class "Default")
      (node (ref "DD1") (pin "G15") (pinfunction "LVDS82p_G15") (pintype "passive"))
    )
    (net (code "121") (name "unconnected-(DD1D-LVDS83n-PadG16)") (class "Default")
      (node (ref "DD1") (pin "G16") (pinfunction "LVDS83n_G16") (pintype "passive"))
    )
    (net (code "122") (name "unconnected-(DD1D-LVDS83p-PadF16)") (class "Default")
      (node (ref "DD1") (pin "F16") (pinfunction "LVDS83p_F16") (pintype "passive"))
    )
    (net (code "123") (name "unconnected-(DD1D-LVDS84n-PadB18)") (class "Default")
      (node (ref "DD1") (pin "B18") (pinfunction "LVDS84n_B18") (pintype "passive"))
    )
    (net (code "124") (name "unconnected-(DD1D-LVDS84p-PadA18)") (class "Default")
      (node (ref "DD1") (pin "A18") (pinfunction "LVDS84p_A18") (pintype "passive"))
    )
    (net (code "125") (name "unconnected-(DD1D-LVDS85n-PadD17)") (class "Default")
      (node (ref "DD1") (pin "D17") (pinfunction "LVDS85n_D17") (pintype "passive"))
    )
    (net (code "126") (name "unconnected-(DD1D-LVDS85p-PadC17)") (class "Default")
      (node (ref "DD1") (pin "C17") (pinfunction "LVDS85p_C17") (pintype "passive"))
    )
    (net (code "127") (name "unconnected-(DD1D-LVDS89n-PadE18)") (class "Default")
      (node (ref "DD1") (pin "E18") (pinfunction "LVDS89n_E18") (pintype "passive"))
    )
    (net (code "128") (name "unconnected-(DD1D-LVDS89p-PadD18)") (class "Default")
      (node (ref "DD1") (pin "D18") (pinfunction "LVDS89p_D18") (pintype "passive"))
    )
    (net (code "129") (name "unconnected-(DD1D-LVDS90n-PadB19)") (class "Default")
      (node (ref "DD1") (pin "B19") (pinfunction "LVDS90n_B19") (pintype "passive"))
    )
    (net (code "130") (name "unconnected-(DD1D-LVDS90p-PadA19)") (class "Default")
      (node (ref "DD1") (pin "A19") (pinfunction "LVDS90p_A19") (pintype "passive"))
    )
    (net (code "131") (name "unconnected-(DD1D-LVDS91n-PadC19)") (class "Default")
      (node (ref "DD1") (pin "C19") (pinfunction "LVDS91n_C19") (pintype "passive"))
    )
    (net (code "132") (name "unconnected-(DD1D-LVDS91p-PadD19)") (class "Default")
      (node (ref "DD1") (pin "D19") (pinfunction "LVDS91p_D19") (pintype "passive"))
    )
    (net (code "133") (name "unconnected-(DD1D-LVDS92n-PadB20)") (class "Default")
      (node (ref "DD1") (pin "B20") (pinfunction "LVDS92n_B20") (pintype "passive"))
    )
    (net (code "134") (name "unconnected-(DD1D-LVDS92p-PadA20)") (class "Default")
      (node (ref "DD1") (pin "A20") (pinfunction "LVDS92p_A20") (pintype "passive"))
    )
    (net (code "135") (name "unconnected-(DD1E-IO4_0-PadD14)") (class "Default")
      (node (ref "DD1") (pin "D14") (pinfunction "IO4_0_D14") (pintype "passive"))
    )
    (net (code "136") (name "unconnected-(DD1E-IO4_1-PadD20)") (class "Default")
      (node (ref "DD1") (pin "D20") (pinfunction "IO4_1_D20") (pintype "passive"))
    )
    (net (code "137") (name "unconnected-(DD1E-LVDS79n-PadE15)") (class "Default")
      (node (ref "DD1") (pin "E15") (pinfunction "LVDS79n_E15") (pintype "passive"))
    )
    (net (code "138") (name "unconnected-(DD1E-LVDS79p-PadD15)") (class "Default")
      (node (ref "DD1") (pin "D15") (pinfunction "LVDS79p_D15") (pintype "passive"))
    )
    (net (code "139") (name "unconnected-(DD1E-LVDS86n-PadF17)") (class "Default")
      (node (ref "DD1") (pin "F17") (pinfunction "LVDS86n_F17") (pintype "passive"))
    )
    (net (code "140") (name "unconnected-(DD1E-LVDS86p-PadG17)") (class "Default")
      (node (ref "DD1") (pin "G17") (pinfunction "LVDS86p_G17") (pintype "passive"))
    )
    (net (code "141") (name "unconnected-(DD1E-LVDS87n-PadJ17)") (class "Default")
      (node (ref "DD1") (pin "J17") (pinfunction "LVDS87n_J17") (pintype "passive"))
    )
    (net (code "142") (name "unconnected-(DD1E-LVDS87p-PadH17)") (class "Default")
      (node (ref "DD1") (pin "H17") (pinfunction "LVDS87p_H17") (pintype "passive"))
    )
    (net (code "143") (name "unconnected-(DD1E-LVDS88n-PadG18)") (class "Default")
      (node (ref "DD1") (pin "G18") (pinfunction "LVDS88n_G18") (pintype "passive"))
    )
    (net (code "144") (name "unconnected-(DD1E-LVDS88p-PadF18)") (class "Default")
      (node (ref "DD1") (pin "F18") (pinfunction "LVDS88p_F18") (pintype "passive"))
    )
    (net (code "145") (name "unconnected-(DD1E-LVDS93n-PadJ16)") (class "Default")
      (node (ref "DD1") (pin "J16") (pinfunction "LVDS93n_J16") (pintype "passive"))
    )
    (net (code "146") (name "unconnected-(DD1E-LVDS93p-PadK16)") (class "Default")
      (node (ref "DD1") (pin "K16") (pinfunction "LVDS93p_K16") (pintype "passive"))
    )
    (net (code "147") (name "unconnected-(DD1E-LVDS94n-PadJ18)") (class "Default")
      (node (ref "DD1") (pin "J18") (pinfunction "LVDS94n_J18") (pintype "passive"))
    )
    (net (code "148") (name "unconnected-(DD1E-LVDS94p-PadK17)") (class "Default")
      (node (ref "DD1") (pin "K17") (pinfunction "LVDS94p_K17") (pintype "passive"))
    )
    (net (code "149") (name "unconnected-(DD1E-LVDS95n-PadB21)") (class "Default")
      (node (ref "DD1") (pin "B21") (pinfunction "LVDS95n_B21") (pintype "passive"))
    )
    (net (code "150") (name "unconnected-(DD1E-LVDS95p-PadA21)") (class "Default")
      (node (ref "DD1") (pin "A21") (pinfunction "LVDS95p_A21") (pintype "passive"))
    )
    (net (code "151") (name "unconnected-(DD1E-LVDS96n-PadA22)") (class "Default")
      (node (ref "DD1") (pin "A22") (pinfunction "LVDS96n_A22") (pintype "passive"))
    )
    (net (code "152") (name "unconnected-(DD1E-LVDS96p-PadB22)") (class "Default")
      (node (ref "DD1") (pin "B22") (pinfunction "LVDS96p_B22") (pintype "passive"))
    )
    (net (code "153") (name "unconnected-(DD1E-LVDS97n-PadB23)") (class "Default")
      (node (ref "DD1") (pin "B23") (pinfunction "LVDS97n_B23") (pintype "passive"))
    )
    (net (code "154") (name "unconnected-(DD1E-LVDS97p-PadA23)") (class "Default")
      (node (ref "DD1") (pin "A23") (pinfunction "LVDS97p_A23") (pintype "passive"))
    )
    (net (code "155") (name "unconnected-(DD1E-LVDS98n-PadC21)") (class "Default")
      (node (ref "DD1") (pin "C21") (pinfunction "LVDS98n_C21") (pintype "passive"))
    )
    (net (code "156") (name "unconnected-(DD1E-LVDS98p-PadD21)") (class "Default")
      (node (ref "DD1") (pin "D21") (pinfunction "LVDS98p_D21") (pintype "passive"))
    )
    (net (code "157") (name "unconnected-(DD1E-LVDS99n-PadC23)") (class "Default")
      (node (ref "DD1") (pin "C23") (pinfunction "LVDS99n_C23") (pintype "passive"))
    )
    (net (code "158") (name "unconnected-(DD1E-LVDS99p-PadC22)") (class "Default")
      (node (ref "DD1") (pin "C22") (pinfunction "LVDS99p_C22") (pintype "passive"))
    )
    (net (code "159") (name "unconnected-(DD1E-LVDSCLK4n-PadB3)") (class "Default")
      (node (ref "DD1") (pin "B3") (pinfunction "LVDSCLK4n_B3") (pintype "passive"))
    )
    (net (code "160") (name "unconnected-(DD1E-LVDSCLK4p-PadA13)") (class "Default")
      (node (ref "DD1") (pin "A13") (pinfunction "LVDSCLK4p_A13") (pintype "passive"))
    )
    (net (code "161") (name "unconnected-(DD1E-VREFB4N0-PadE20)") (class "Default")
      (node (ref "DD1") (pin "E20") (pinfunction "VREFB4N0_E20") (pintype "passive"))
    )
    (net (code "162") (name "unconnected-(DD1E-VREFB4N1-PadD16)") (class "Default")
      (node (ref "DD1") (pin "D16") (pinfunction "VREFB4N1_D16") (pintype "passive"))
    )
    (net (code "163") (name "unconnected-(DD1F-LVDS152n-PadAB21)") (class "Default")
      (node (ref "DD1") (pin "AB21") (pinfunction "LVDS152n_AB21") (pintype "passive"))
    )
    (net (code "164") (name "unconnected-(DD1F-LVDS152p-PadAC22)") (class "Default")
      (node (ref "DD1") (pin "AC22") (pinfunction "LVDS152p_AC22") (pintype "passive"))
    )
    (net (code "165") (name "unconnected-(DD1F-LVDS154n-PadAD21)") (class "Default")
      (node (ref "DD1") (pin "AD21") (pinfunction "LVDS154n_AD21") (pintype "passive"))
    )
    (net (code "166") (name "unconnected-(DD1F-LVDS154p-PadAC21)") (class "Default")
      (node (ref "DD1") (pin "AC21") (pinfunction "LVDS154p_AC21") (pintype "passive"))
    )
    (net (code "167") (name "unconnected-(DD1F-LVDS156n-PadW19)") (class "Default")
      (node (ref "DD1") (pin "W19") (pinfunction "LVDS156n_W19") (pintype "passive"))
    )
    (net (code "168") (name "unconnected-(DD1F-LVDS156p-PadV18)") (class "Default")
      (node (ref "DD1") (pin "V18") (pinfunction "LVDS156p_V18") (pintype "passive"))
    )
    (net (code "169") (name "unconnected-(DD1F-LVDS157n-PadU18)") (class "Default")
      (node (ref "DD1") (pin "U18") (pinfunction "LVDS157n_U18") (pintype "passive"))
    )
    (net (code "170") (name "unconnected-(DD1F-LVDS157p-PadU17)") (class "Default")
      (node (ref "DD1") (pin "U17") (pinfunction "LVDS157p_U17") (pintype "passive"))
    )
    (net (code "171") (name "unconnected-(DD1F-LVDS161n-PadAC19)") (class "Default")
      (node (ref "DD1") (pin "AC19") (pinfunction "LVDS161n_AC19") (pintype "passive"))
    )
    (net (code "172") (name "unconnected-(DD1F-LVDS161p-PadAD19)") (class "Default")
      (node (ref "DD1") (pin "AD19") (pinfunction "LVDS161p_AD19") (pintype "passive"))
    )
    (net (code "173") (name "unconnected-(DD1F-LVDS162n-PadAA18)") (class "Default")
      (node (ref "DD1") (pin "AA18") (pinfunction "LVDS162n_AA18") (pintype "passive"))
    )
    (net (code "174") (name "unconnected-(DD1F-LVDS162p-PadAA17)") (class "Default")
      (node (ref "DD1") (pin "AA17") (pinfunction "LVDS162p_AA17") (pintype "passive"))
    )
    (net (code "175") (name "unconnected-(DD1F-LVDS163n-PadV17)") (class "Default")
      (node (ref "DD1") (pin "V17") (pinfunction "LVDS163n_V17") (pintype "passive"))
    )
    (net (code "176") (name "unconnected-(DD1F-LVDS163p-PadW17)") (class "Default")
      (node (ref "DD1") (pin "W17") (pinfunction "LVDS163p_W17") (pintype "passive"))
    )
    (net (code "177") (name "unconnected-(DD1F-LVDS164n-PadAC18)") (class "Default")
      (node (ref "DD1") (pin "AC18") (pinfunction "LVDS164n_AC18") (pintype "passive"))
    )
    (net (code "178") (name "unconnected-(DD1F-LVDS164p-PadAB18)") (class "Default")
      (node (ref "DD1") (pin "AB18") (pinfunction "LVDS164p_AB18") (pintype "passive"))
    )
    (net (code "179") (name "unconnected-(DD1F-LVDS166n-PadAE18)") (class "Default")
      (node (ref "DD1") (pin "AE18") (pinfunction "LVDS166n_AE18") (pintype "passive"))
    )
    (net (code "180") (name "unconnected-(DD1F-LVDS166p-PadAF18)") (class "Default")
      (node (ref "DD1") (pin "AF18") (pinfunction "LVDS166p_AF18") (pintype "passive"))
    )
    (net (code "181") (name "unconnected-(DD1F-LVDS167n-PadY16)") (class "Default")
      (node (ref "DD1") (pin "Y16") (pinfunction "LVDS167n_Y16") (pintype "passive"))
    )
    (net (code "182") (name "unconnected-(DD1F-LVDS167p-PadAA16)") (class "Default")
      (node (ref "DD1") (pin "AA16") (pinfunction "LVDS167p_AA16") (pintype "passive"))
    )
    (net (code "183") (name "unconnected-(DD1F-LVDS168n-PadAD17)") (class "Default")
      (node (ref "DD1") (pin "AD17") (pinfunction "LVDS168n_AD17") (pintype "passive"))
    )
    (net (code "184") (name "unconnected-(DD1G-IO7_0-PadAA20)") (class "Default")
      (node (ref "DD1") (pin "AA20") (pinfunction "IO7_0_AA20") (pintype "passive"))
    )
    (net (code "185") (name "unconnected-(DD1G-IO7_1-PadAC14)") (class "Default")
      (node (ref "DD1") (pin "AC14") (pinfunction "IO7_1_AC14") (pintype "passive"))
    )
    (net (code "186") (name "unconnected-(DD1G-LVDS159n-PadAC20)") (class "Default")
      (node (ref "DD1") (pin "AC20") (pinfunction "LVDS159n_AC20") (pintype "passive"))
    )
    (net (code "187") (name "unconnected-(DD1G-LVDS159p-PadAB20)") (class "Default")
      (node (ref "DD1") (pin "AB20") (pinfunction "LVDS159p_AB20") (pintype "passive"))
    )
    (net (code "188") (name "unconnected-(DD1G-LVDS168p-PadAC17)") (class "Default")
      (node (ref "DD1") (pin "AC17") (pinfunction "LVDS168p_AC17") (pintype "passive"))
    )
    (net (code "189") (name "unconnected-(DD1G-LVDS170n-PadW16)") (class "Default")
      (node (ref "DD1") (pin "W16") (pinfunction "LVDS170n_W16") (pintype "passive"))
    )
    (net (code "190") (name "unconnected-(DD1G-LVDS170p-PadW15)") (class "Default")
      (node (ref "DD1") (pin "W15") (pinfunction "LVDS170p_W15") (pintype "passive"))
    )
    (net (code "191") (name "unconnected-(DD1G-LVDS171n-PadAD16)") (class "Default")
      (node (ref "DD1") (pin "AD16") (pinfunction "LVDS171n_AD16") (pintype "passive"))
    )
    (net (code "192") (name "unconnected-(DD1G-LVDS171p-PadAE16)") (class "Default")
      (node (ref "DD1") (pin "AE16") (pinfunction "LVDS171p_AE16") (pintype "passive"))
    )
    (net (code "193") (name "unconnected-(DD1G-LVDS172n-PadAC15)") (class "Default")
      (node (ref "DD1") (pin "AC15") (pinfunction "LVDS172n_AC15") (pintype "passive"))
    )
    (net (code "194") (name "unconnected-(DD1G-LVDS172p-PadAB15)") (class "Default")
      (node (ref "DD1") (pin "AB15") (pinfunction "LVDS172p_AB15") (pintype "passive"))
    )
    (net (code "195") (name "unconnected-(DD1G-LVDS173n-PadAA15)") (class "Default")
      (node (ref "DD1") (pin "AA15") (pinfunction "LVDS173n_AA15") (pintype "passive"))
    )
    (net (code "196") (name "unconnected-(DD1G-LVDS173p-PadY15)") (class "Default")
      (node (ref "DD1") (pin "Y15") (pinfunction "LVDS173p_Y15") (pintype "passive"))
    )
    (net (code "197") (name "unconnected-(DD1G-LVDS174n-PadY14)") (class "Default")
      (node (ref "DD1") (pin "Y14") (pinfunction "LVDS174n_Y14") (pintype "passive"))
    )
    (net (code "198") (name "unconnected-(DD1G-LVDS174p-PadAA14)") (class "Default")
      (node (ref "DD1") (pin "AA14") (pinfunction "LVDS174p_AA14") (pintype "passive"))
    )
    (net (code "199") (name "unconnected-(DD1G-LVDS175n-PadY13)") (class "Default")
      (node (ref "DD1") (pin "Y13") (pinfunction "LVDS175n_Y13") (pintype "passive"))
    )
    (net (code "200") (name "unconnected-(DD1G-LVDS175p-PadAA13)") (class "Default")
      (node (ref "DD1") (pin "AA13") (pinfunction "LVDS175p_AA13") (pintype "passive"))
    )
    (net (code "201") (name "unconnected-(DD1G-LVDS176n-PadAD15)") (class "Default")
      (node (ref "DD1") (pin "AD15") (pinfunction "LVDS176n_AD15") (pintype "passive"))
    )
    (net (code "202") (name "unconnected-(DD1G-LVDS176p-PadAE15)") (class "Default")
      (node (ref "DD1") (pin "AE15") (pinfunction "LVDS176p_AE15") (pintype "passive"))
    )
    (net (code "203") (name "unconnected-(DD1G-VREFB7N0-PadY18)") (class "Default")
      (node (ref "DD1") (pin "Y18") (pinfunction "VREFB7N0_Y18") (pintype "passive"))
    )
    (net (code "204") (name "unconnected-(DD1G-VREFB7N1-PadAC16)") (class "Default")
      (node (ref "DD1") (pin "AC16") (pinfunction "VREFB7N1_AC16") (pintype "passive"))
    )
    (net (code "205") (name "unconnected-(DD1H-LVDS178p-PadAD12)") (class "Default")
      (node (ref "DD1") (pin "AD12") (pinfunction "LVDS178p_AD12") (pintype "passive"))
    )
    (net (code "206") (name "unconnected-(DD1H-LVDS179n-PadY12)") (class "Default")
      (node (ref "DD1") (pin "Y12") (pinfunction "LVDS179n_Y12") (pintype "passive"))
    )
    (net (code "207") (name "unconnected-(DD1H-LVDS179p-PadAA12)") (class "Default")
      (node (ref "DD1") (pin "AA12") (pinfunction "LVDS179p_AA12") (pintype "passive"))
    )
    (net (code "208") (name "unconnected-(DD1H-LVDS180n-PadU12)") (class "Default")
      (node (ref "DD1") (pin "U12") (pinfunction "LVDS180n_U12") (pintype "passive"))
    )
    (net (code "209") (name "unconnected-(DD1H-LVDS180p-PadV11)") (class "Default")
      (node (ref "DD1") (pin "V11") (pinfunction "LVDS180p_V11") (pintype "passive"))
    )
    (net (code "210") (name "unconnected-(DD1H-LVDS186n-PadAC10)") (class "Default")
      (node (ref "DD1") (pin "AC10") (pinfunction "LVDS186n_AC10") (pintype "passive"))
    )
    (net (code "211") (name "unconnected-(DD1H-LVDS186p-PadAC9)") (class "Default")
      (node (ref "DD1") (pin "AC9") (pinfunction "LVDS186p_AC9") (pintype "passive"))
    )
    (net (code "212") (name "unconnected-(DD1H-LVDS187n-PadW12)") (class "Default")
      (node (ref "DD1") (pin "W12") (pinfunction "LVDS187n_W12") (pintype "passive"))
    )
    (net (code "213") (name "unconnected-(DD1H-LVDS187p-PadW11)") (class "Default")
      (node (ref "DD1") (pin "W11") (pinfunction "LVDS187p_W11") (pintype "passive"))
    )
    (net (code "214") (name "unconnected-(DD1H-LVDS188n-PadAF8)") (class "Default")
      (node (ref "DD1") (pin "AF8") (pinfunction "LVDS188n_AF8") (pintype "passive"))
    )
    (net (code "215") (name "unconnected-(DD1H-LVDS188p-PadAE8)") (class "Default")
      (node (ref "DD1") (pin "AE8") (pinfunction "LVDS188p_AE8") (pintype "passive"))
    )
    (net (code "216") (name "unconnected-(DD1H-LVDS189p-PadAE7)") (class "Default")
      (node (ref "DD1") (pin "AE7") (pinfunction "LVDS189p_AE7") (pintype "passive"))
    )
    (net (code "217") (name "unconnected-(DD1H-LVDS190n-PadY11)") (class "Default")
      (node (ref "DD1") (pin "Y11") (pinfunction "LVDS190n_Y11") (pintype "passive"))
    )
    (net (code "218") (name "unconnected-(DD1H-LVDS190p-PadAA11)") (class "Default")
      (node (ref "DD1") (pin "AA11") (pinfunction "LVDS190p_AA11") (pintype "passive"))
    )
    (net (code "219") (name "unconnected-(DD1H-LVDS191n-PadAB10)") (class "Default")
      (node (ref "DD1") (pin "AB10") (pinfunction "LVDS191n_AB10") (pintype "passive"))
    )
    (net (code "220") (name "unconnected-(DD1H-LVDS191p-PadAA10)") (class "Default")
      (node (ref "DD1") (pin "AA10") (pinfunction "LVDS191p_AA10") (pintype "passive"))
    )
    (net (code "221") (name "unconnected-(DD1H-LVDS192n-PadAF6)") (class "Default")
      (node (ref "DD1") (pin "AF6") (pinfunction "LVDS192n_AF6") (pintype "passive"))
    )
    (net (code "222") (name "unconnected-(DD1H-LVDS192p-PadAE6)") (class "Default")
      (node (ref "DD1") (pin "AE6") (pinfunction "LVDS192p_AE6") (pintype "passive"))
    )
    (net (code "223") (name "unconnected-(DD1H-LVDS193n-PadAD8)") (class "Default")
      (node (ref "DD1") (pin "AD8") (pinfunction "LVDS193n_AD8") (pintype "passive"))
    )
    (net (code "224") (name "unconnected-(DD1I-IO8_0-PadW8)") (class "Default")
      (node (ref "DD1") (pin "W8") (pinfunction "IO8_0_W8") (pintype "passive"))
    )
    (net (code "225") (name "unconnected-(DD1I-IO8_1-PadAA9)") (class "Default")
      (node (ref "DD1") (pin "AA9") (pinfunction "IO8_1_AA9") (pintype "passive"))
    )
    (net (code "226") (name "unconnected-(DD1I-IO8_2-PadAB8)") (class "Default")
      (node (ref "DD1") (pin "AB8") (pinfunction "IO8_2_AB8") (pintype "passive"))
    )
    (net (code "227") (name "unconnected-(DD1I-IO8_3-PadAB12)") (class "Default")
      (node (ref "DD1") (pin "AB12") (pinfunction "IO8_3_AB12") (pintype "passive"))
    )
    (net (code "228") (name "unconnected-(DD1I-LVDS181n-PadV13)") (class "Default")
      (node (ref "DD1") (pin "V13") (pinfunction "LVDS181n_V13") (pintype "passive"))
    )
    (net (code "229") (name "unconnected-(DD1I-LVDS181p-PadV14)") (class "Default")
      (node (ref "DD1") (pin "V14") (pinfunction "LVDS181p_V14") (pintype "passive"))
    )
    (net (code "230") (name "unconnected-(DD1I-LVDS182p-PadAD11)") (class "Default")
      (node (ref "DD1") (pin "AD11") (pinfunction "LVDS182p_AD11") (pintype "passive"))
    )
    (net (code "231") (name "unconnected-(DD1I-LVDS184n-PadAC11)") (class "Default")
      (node (ref "DD1") (pin "AC11") (pinfunction "LVDS184n_AC11") (pintype "passive"))
    )
    (net (code "232") (name "unconnected-(DD1I-LVDS184p-PadAD10)") (class "Default")
      (node (ref "DD1") (pin "AD10") (pinfunction "LVDS184p_AD10") (pintype "passive"))
    )
    (net (code "233") (name "unconnected-(DD1I-LVDS193p-PadAC8)") (class "Default")
      (node (ref "DD1") (pin "AC8") (pinfunction "LVDS193p_AC8") (pintype "passive"))
    )
    (net (code "234") (name "unconnected-(DD1I-LVDS194n-PadY10)") (class "Default")
      (node (ref "DD1") (pin "Y10") (pinfunction "LVDS194n_Y10") (pintype "passive"))
    )
    (net (code "235") (name "unconnected-(DD1I-LVDS194p-PadW10)") (class "Default")
      (node (ref "DD1") (pin "W10") (pinfunction "LVDS194p_W10") (pintype "passive"))
    )
    (net (code "236") (name "unconnected-(DD1I-LVDS195n-PadV9)") (class "Default")
      (node (ref "DD1") (pin "V9") (pinfunction "LVDS195n_V9") (pintype "passive"))
    )
    (net (code "237") (name "unconnected-(DD1I-LVDS195p-PadV10)") (class "Default")
      (node (ref "DD1") (pin "V10") (pinfunction "LVDS195p_V10") (pintype "passive"))
    )
    (net (code "238") (name "unconnected-(DD1I-LVDS196n-PadAD7)") (class "Default")
      (node (ref "DD1") (pin "AD7") (pinfunction "LVDS196n_AD7") (pintype "passive"))
    )
    (net (code "239") (name "unconnected-(DD1I-LVDS196p-PadAD6)") (class "Default")
      (node (ref "DD1") (pin "AD6") (pinfunction "LVDS196p_AD6") (pintype "passive"))
    )
    (net (code "240") (name "unconnected-(DD1I-LVDS197n-PadAF5)") (class "Default")
      (node (ref "DD1") (pin "AF5") (pinfunction "LVDS197n_AF5") (pintype "passive"))
    )
    (net (code "241") (name "unconnected-(DD1I-LVDS197p-PadAE5)") (class "Default")
      (node (ref "DD1") (pin "AE5") (pinfunction "LVDS197p_AE5") (pintype "passive"))
    )
    (net (code "242") (name "unconnected-(DD1I-LVDS198n-PadAD5)") (class "Default")
      (node (ref "DD1") (pin "AD5") (pinfunction "LVDS198n_AD5") (pintype "passive"))
    )
    (net (code "243") (name "unconnected-(DD1I-LVDS198p-PadAD4)") (class "Default")
      (node (ref "DD1") (pin "AD4") (pinfunction "LVDS198p_AD4") (pintype "passive"))
    )
    (net (code "244") (name "unconnected-(DD1I-LVDS199n-PadAC6)") (class "Default")
      (node (ref "DD1") (pin "AC6") (pinfunction "LVDS199n_AC6") (pintype "passive"))
    )
    (net (code "245") (name "unconnected-(DD1I-LVDS199p-PadAC5)") (class "Default")
      (node (ref "DD1") (pin "AC5") (pinfunction "LVDS199p_AC5") (pintype "passive"))
    )
    (net (code "246") (name "unconnected-(DD1I-LVDS200n-PadAE4)") (class "Default")
      (node (ref "DD1") (pin "AE4") (pinfunction "LVDS200n_AE4") (pintype "passive"))
    )
    (net (code "247") (name "unconnected-(DD1I-LVDS200p-PadAF4)") (class "Default")
      (node (ref "DD1") (pin "AF4") (pinfunction "LVDS200p_AF4") (pintype "passive"))
    )
    (net (code "248") (name "unconnected-(DD1I-LVDSCLK7n-PadAD13)") (class "Default")
      (node (ref "DD1") (pin "AD13") (pinfunction "LVDSCLK7n_AD13") (pintype "passive"))
    )
    (net (code "249") (name "unconnected-(DD1I-LVDSCLK7p-PadAC13)") (class "Default")
      (node (ref "DD1") (pin "AC13") (pinfunction "LVDSCLK7p_AC13") (pintype "passive"))
    )
    (net (code "250") (name "unconnected-(DD1I-VREFB8N0-PadAC12)") (class "Default")
      (node (ref "DD1") (pin "AC12") (pinfunction "VREFB8N0_AC12") (pintype "passive"))
    )
    (net (code "251") (name "unconnected-(DD1I-VREFB8N1-PadAC7)") (class "Default")
      (node (ref "DD1") (pin "AC7") (pinfunction "VREFB8N1_AC7") (pintype "passive"))
    )
    (net (code "252") (name "unconnected-(DD1N-IO1_1-PadV7)") (class "Default")
      (node (ref "DD1") (pin "V7") (pinfunction "IO1_1_V7") (pintype "passive"))
    )
    (net (code "253") (name "unconnected-(DD1N-LVDS3p-PadAA5)") (class "Default")
      (node (ref "DD1") (pin "AA5") (pinfunction "LVDS3p_AA5") (pintype "passive"))
    )
    (net (code "254") (name "unconnected-(DD1N-LVDS4n-PadAC1)") (class "Default")
      (node (ref "DD1") (pin "AC1") (pinfunction "LVDS4n_AC1") (pintype "passive"))
    )
    (net (code "255") (name "unconnected-(DD1N-LVDS4p-PadAC2)") (class "Default")
      (node (ref "DD1") (pin "AC2") (pinfunction "LVDS4p_AC2") (pintype "passive"))
    )
    (net (code "256") (name "unconnected-(DD1N-LVDS5n-PadAA3)") (class "Default")
      (node (ref "DD1") (pin "AA3") (pinfunction "LVDS5n_AA3") (pintype "passive"))
    )
    (net (code "257") (name "unconnected-(DD1N-LVDS5p-PadAA4)") (class "Default")
      (node (ref "DD1") (pin "AA4") (pinfunction "LVDS5p_AA4") (pintype "passive"))
    )
    (net (code "258") (name "unconnected-(DD1N-LVDS6n-PadAB1)") (class "Default")
      (node (ref "DD1") (pin "AB1") (pinfunction "LVDS6n_AB1") (pintype "passive"))
    )
    (net (code "259") (name "unconnected-(DD1N-LVDS6p-PadAB2)") (class "Default")
      (node (ref "DD1") (pin "AB2") (pinfunction "LVDS6p_AB2") (pintype "passive"))
    )
    (net (code "260") (name "unconnected-(DD1N-LVDS7n-PadT8)") (class "Default")
      (node (ref "DD1") (pin "T8") (pinfunction "LVDS7n_T8") (pintype "passive"))
    )
    (net (code "261") (name "unconnected-(DD1N-LVDS7p-PadR8)") (class "Default")
      (node (ref "DD1") (pin "R8") (pinfunction "LVDS7p_R8") (pintype "passive"))
    )
    (net (code "262") (name "unconnected-(DD1N-LVDS8n-PadY4)") (class "Default")
      (node (ref "DD1") (pin "Y4") (pinfunction "LVDS8n_Y4") (pintype "passive"))
    )
    (net (code "263") (name "unconnected-(DD1N-LVDS8p-PadY3)") (class "Default")
      (node (ref "DD1") (pin "Y3") (pinfunction "LVDS8p_Y3") (pintype "passive"))
    )
    (net (code "264") (name "unconnected-(DD1N-LVDS9n-PadAA1)") (class "Default")
      (node (ref "DD1") (pin "AA1") (pinfunction "LVDS9n_AA1") (pintype "passive"))
    )
    (net (code "265") (name "unconnected-(DD1N-LVDS9p-PadAA2)") (class "Default")
      (node (ref "DD1") (pin "AA2") (pinfunction "LVDS9p_AA2") (pintype "passive"))
    )
    (net (code "266") (name "unconnected-(DD1N-LVDS10n-PadV6)") (class "Default")
      (node (ref "DD1") (pin "V6") (pinfunction "LVDS10n_V6") (pintype "passive"))
    )
    (net (code "267") (name "unconnected-(DD1N-LVDS18p-PadU9)") (class "Default")
      (node (ref "DD1") (pin "U9") (pinfunction "LVDS18p_U9") (pintype "passive"))
    )
    (net (code "268") (name "unconnected-(DD1N-LVDS19n-PadU1)") (class "Default")
      (node (ref "DD1") (pin "U1") (pinfunction "LVDS19n_U1") (pintype "passive"))
    )
    (net (code "269") (name "unconnected-(DD1N-LVDS19p-PadU2)") (class "Default")
      (node (ref "DD1") (pin "U2") (pinfunction "LVDS19p_U2") (pintype "passive"))
    )
    (net (code "270") (name "unconnected-(DD1N-LVDS20n-PadR7)") (class "Default")
      (node (ref "DD1") (pin "R7") (pinfunction "LVDS20n_R7") (pintype "passive"))
    )
    (net (code "271") (name "unconnected-(DD1N-LVDS20p-PadR6)") (class "Default")
      (node (ref "DD1") (pin "R6") (pinfunction "LVDS20p_R6") (pintype "passive"))
    )
    (net (code "272") (name "unconnected-(DD1N-LVDS21n-PadT3)") (class "Default")
      (node (ref "DD1") (pin "T3") (pinfunction "LVDS21n_T3") (pintype "passive"))
    )
    (net (code "273") (name "unconnected-(DD1N-LVDS21p-PadT2)") (class "Default")
      (node (ref "DD1") (pin "T2") (pinfunction "LVDS21p_T2") (pintype "passive"))
    )
    (net (code "274") (name "unconnected-(DD1N-LVDS22n-PadP6)") (class "Default")
      (node (ref "DD1") (pin "P6") (pinfunction "LVDS22n_P6") (pintype "passive"))
    )
    (net (code "275") (name "unconnected-(DD1N-LVDS22p-PadP7)") (class "Default")
      (node (ref "DD1") (pin "P7") (pinfunction "LVDS22p_P7") (pintype "passive"))
    )
    (net (code "276") (name "unconnected-(DD1N-LVDS23n-PadT9)") (class "Default")
      (node (ref "DD1") (pin "T9") (pinfunction "LVDS23n_T9") (pintype "passive"))
    )
    (net (code "277") (name "unconnected-(DD1N-LVDS24n-PadR5)") (class "Default")
      (node (ref "DD1") (pin "R5") (pinfunction "LVDS24n_R5") (pintype "passive"))
    )
    (net (code "278") (name "unconnected-(DD1N-LVDS24p-PadR4)") (class "Default")
      (node (ref "DD1") (pin "R4") (pinfunction "LVDS24p_R4") (pintype "passive"))
    )
    (net (code "279") (name "unconnected-(DD1N-LVDS25n-PadR3)") (class "Default")
      (node (ref "DD1") (pin "R3") (pinfunction "LVDS25n_R3") (pintype "passive"))
    )
    (net (code "280") (name "unconnected-(DD1N-VREFB1N0-PadT4)") (class "Default")
      (node (ref "DD1") (pin "T4") (pinfunction "VREFB1N0_T4") (pintype "passive"))
    )
    (net (code "281") (name "unconnected-(DD1N-VREFB1N1-PadW6)") (class "Default")
      (node (ref "DD1") (pin "W6") (pinfunction "VREFB1N1_W6") (pintype "passive"))
    )
    (net (code "282") (name "unconnected-(DD1O-CLK1-PadN1)") (class "Default")
      (node (ref "DD1") (pin "N1") (pinfunction "CLK1_N1") (pintype "passive"))
    )
    (net (code "283") (name "unconnected-(DD1O-CLK2-PadP2)") (class "Default")
      (node (ref "DD1") (pin "P2") (pinfunction "CLK2_P2") (pintype "passive"))
    )
    (net (code "284") (name "unconnected-(DD1O-CLK3-PadP1)") (class "Default")
      (node (ref "DD1") (pin "P1") (pinfunction "CLK3_P1") (pintype "passive"))
    )
    (net (code "285") (name "unconnected-(DD1O-IO1_0-PadU5)") (class "Default")
      (node (ref "DD1") (pin "U5") (pinfunction "IO1_0_U5") (pintype "passive"))
    )
    (net (code "286") (name "unconnected-(DD1O-IO1_2-PadY1)") (class "Default")
      (node (ref "DD1") (pin "Y1") (pinfunction "IO1_2_Y1") (pintype "passive"))
    )
    (net (code "287") (name "unconnected-(DD1O-IO1_3-PadAC3)") (class "Default")
      (node (ref "DD1") (pin "AC3") (pinfunction "IO1_3_AC3") (pintype "passive"))
    )
    (net (code "288") (name "unconnected-(DD1O-LVDS0n-PadAB4)") (class "Default")
      (node (ref "DD1") (pin "AB4") (pinfunction "LVDS0n_AB4") (pintype "passive"))
    )
    (net (code "289") (name "unconnected-(DD1O-LVDS0p-PadAB3)") (class "Default")
      (node (ref "DD1") (pin "AB3") (pinfunction "LVDS0p_AB3") (pintype "passive"))
    )
    (net (code "290") (name "unconnected-(DD1O-LVDS1n-PadAE3)") (class "Default")
      (node (ref "DD1") (pin "AE3") (pinfunction "LVDS1n_AE3") (pintype "passive"))
    )
    (net (code "291") (name "unconnected-(DD1O-LVDS1p-PadAE2)") (class "Default")
      (node (ref "DD1") (pin "AE2") (pinfunction "LVDS1p_AE2") (pintype "passive"))
    )
    (net (code "292") (name "unconnected-(DD1O-LVDS2n-PadAD3)") (class "Default")
      (node (ref "DD1") (pin "AD3") (pinfunction "LVDS2n_AD3") (pintype "passive"))
    )
    (net (code "293") (name "unconnected-(DD1O-LVDS2p-PadAD2)") (class "Default")
      (node (ref "DD1") (pin "AD2") (pinfunction "LVDS2p_AD2") (pintype "passive"))
    )
    (net (code "294") (name "unconnected-(DD1O-LVDS3n-PadY5)") (class "Default")
      (node (ref "DD1") (pin "Y5") (pinfunction "LVDS3n_Y5") (pintype "passive"))
    )
    (net (code "295") (name "unconnected-(DD1O-LVDS10p-PadV5)") (class "Default")
      (node (ref "DD1") (pin "V5") (pinfunction "LVDS10p_V5") (pintype "passive"))
    )
    (net (code "296") (name "unconnected-(DD1O-LVDS11n-PadW3)") (class "Default")
      (node (ref "DD1") (pin "W3") (pinfunction "LVDS11n_W3") (pintype "passive"))
    )
    (net (code "297") (name "unconnected-(DD1O-LVDS11p-PadW4)") (class "Default")
      (node (ref "DD1") (pin "W4") (pinfunction "LVDS11p_W4") (pintype "passive"))
    )
    (net (code "298") (name "unconnected-(DD1O-LVDS12n-PadU7)") (class "Default")
      (node (ref "DD1") (pin "U7") (pinfunction "LVDS12n_U7") (pintype "passive"))
    )
    (net (code "299") (name "unconnected-(DD1O-LVDS12p-PadU6)") (class "Default")
      (node (ref "DD1") (pin "U6") (pinfunction "LVDS12p_U6") (pintype "passive"))
    )
    (net (code "300") (name "unconnected-(DD1O-LVDS13n-PadW1)") (class "Default")
      (node (ref "DD1") (pin "W1") (pinfunction "LVDS13n_W1") (pintype "passive"))
    )
    (net (code "301") (name "unconnected-(DD1O-LVDS13p-PadW2)") (class "Default")
      (node (ref "DD1") (pin "W2") (pinfunction "LVDS13p_W2") (pintype "passive"))
    )
    (net (code "302") (name "unconnected-(DD1O-LVDS14n-PadV3)") (class "Default")
      (node (ref "DD1") (pin "V3") (pinfunction "LVDS14n_V3") (pintype "passive"))
    )
    (net (code "303") (name "unconnected-(DD1O-LVDS14p-PadV4)") (class "Default")
      (node (ref "DD1") (pin "V4") (pinfunction "LVDS14p_V4") (pintype "passive"))
    )
    (net (code "304") (name "unconnected-(DD1O-LVDS15n-PadT6)") (class "Default")
      (node (ref "DD1") (pin "T6") (pinfunction "LVDS15n_T6") (pintype "passive"))
    )
    (net (code "305") (name "unconnected-(DD1O-LVDS15p-PadT7)") (class "Default")
      (node (ref "DD1") (pin "T7") (pinfunction "LVDS15p_T7") (pintype "passive"))
    )
    (net (code "306") (name "unconnected-(DD1O-LVDS16n-PadV2)") (class "Default")
      (node (ref "DD1") (pin "V2") (pinfunction "LVDS16n_V2") (pintype "passive"))
    )
    (net (code "307") (name "unconnected-(DD1O-LVDS16p-PadV1)") (class "Default")
      (node (ref "DD1") (pin "V1") (pinfunction "LVDS16p_V1") (pintype "passive"))
    )
    (net (code "308") (name "unconnected-(DD1O-LVDS17n-PadU4)") (class "Default")
      (node (ref "DD1") (pin "U4") (pinfunction "LVDS17n_U4") (pintype "passive"))
    )
    (net (code "309") (name "unconnected-(DD1O-LVDS17p-PadU3)") (class "Default")
      (node (ref "DD1") (pin "U3") (pinfunction "LVDS17p_U3") (pintype "passive"))
    )
    (net (code "310") (name "unconnected-(DD1O-LVDS18n-PadU10)") (class "Default")
      (node (ref "DD1") (pin "U10") (pinfunction "LVDS18n_U10") (pintype "passive"))
    )
    (net (code "311") (name "unconnected-(DD1O-LVDS23p-PadT10)") (class "Default")
      (node (ref "DD1") (pin "T10") (pinfunction "LVDS23p_T10") (pintype "passive"))
    )
    (net (code "312") (name "unconnected-(DD1O-LVDS25p-PadR2)") (class "Default")
      (node (ref "DD1") (pin "R2") (pinfunction "LVDS25p_R2") (pintype "passive"))
    )
    (net (code "313") (name "unconnected-(DD1O-LVDS26n-PadP4)") (class "Default")
      (node (ref "DD1") (pin "P4") (pinfunction "LVDS26n_P4") (pintype "passive"))
    )
    (net (code "314") (name "unconnected-(DD1O-LVDS26p-PadP3)") (class "Default")
      (node (ref "DD1") (pin "P3") (pinfunction "LVDS26p_P3") (pintype "passive"))
    )
    (net (code "315") (name "unconnected-(DD1O-LVDS27n-PadM2)") (class "Default")
      (node (ref "DD1") (pin "M2") (pinfunction "LVDS27n_M2") (pintype "passive"))
    )
    (net (code "316") (name "unconnected-(DD1O-LVDS27p-PadM3)") (class "Default")
      (node (ref "DD1") (pin "M3") (pinfunction "LVDS27p_M3") (pintype "passive"))
    )
    (net (code "317") (name "unconnected-(DD1O-LVDS28n-PadM5)") (class "Default")
      (node (ref "DD1") (pin "M5") (pinfunction "LVDS28n_M5") (pintype "passive"))
    )
    (net (code "318") (name "unconnected-(DD1O-LVDS28p-PadM4)") (class "Default")
      (node (ref "DD1") (pin "M4") (pinfunction "LVDS28p_M4") (pintype "passive"))
    )
    (net (code "319") (name "unconnected-(DD1O-PLL1_OUTn-PadAA6)") (class "Default")
      (node (ref "DD1") (pin "AA6") (pinfunction "PLL1_OUTn_AA6") (pintype "passive"))
    )
    (net (code "320") (name "unconnected-(DD1O-PLL1_OUTp-PadAA7)") (class "Default")
      (node (ref "DD1") (pin "AA7") (pinfunction "PLL1_OUTp_AA7") (pintype "passive"))
    )
    (net (code "321") (name "unconnected-(DD1P-IO2_3-PadL9)") (class "Default")
      (node (ref "DD1") (pin "L9") (pinfunction "IO2_3_L9") (pintype "passive"))
    )
    (net (code "322") (name "unconnected-(DD1P-LVDS29n-PadL3)") (class "Default")
      (node (ref "DD1") (pin "L3") (pinfunction "LVDS29n_L3") (pintype "passive"))
    )
    (net (code "323") (name "unconnected-(DD1P-LVDS29p-PadL2)") (class "Default")
      (node (ref "DD1") (pin "L2") (pinfunction "LVDS29p_L2") (pintype "passive"))
    )
    (net (code "324") (name "unconnected-(DD1P-LVDS30n-PadL6)") (class "Default")
      (node (ref "DD1") (pin "L6") (pinfunction "LVDS30n_L6") (pintype "passive"))
    )
    (net (code "325") (name "unconnected-(DD1P-LVDS30p-PadL7)") (class "Default")
      (node (ref "DD1") (pin "L7") (pinfunction "LVDS30p_L7") (pintype "passive"))
    )
    (net (code "326") (name "unconnected-(DD1P-LVDS31n-PadP9)") (class "Default")
      (node (ref "DD1") (pin "P9") (pinfunction "LVDS31n_P9") (pintype "passive"))
    )
    (net (code "327") (name "unconnected-(DD1P-LVDS31p-PadN9)") (class "Default")
      (node (ref "DD1") (pin "N9") (pinfunction "LVDS31p_N9") (pintype "passive"))
    )
    (net (code "328") (name "unconnected-(DD1P-LVDS32n-PadK2)") (class "Default")
      (node (ref "DD1") (pin "K2") (pinfunction "LVDS32n_K2") (pintype "passive"))
    )
    (net (code "329") (name "unconnected-(DD1P-LVDS32p-PadK1)") (class "Default")
      (node (ref "DD1") (pin "K1") (pinfunction "LVDS32p_K1") (pintype "passive"))
    )
    (net (code "330") (name "unconnected-(DD1P-LVDS33n-PadK3)") (class "Default")
      (node (ref "DD1") (pin "K3") (pinfunction "LVDS33n_K3") (pintype "passive"))
    )
    (net (code "331") (name "unconnected-(DD1P-LVDS33p-PadK4)") (class "Default")
      (node (ref "DD1") (pin "K4") (pinfunction "LVDS33p_K4") (pintype "passive"))
    )
    (net (code "332") (name "unconnected-(DD1P-LVDS34n-PadJ1)") (class "Default")
      (node (ref "DD1") (pin "J1") (pinfunction "LVDS34n_J1") (pintype "passive"))
    )
    (net (code "333") (name "unconnected-(DD1P-LVDS34p-PadJ2)") (class "Default")
      (node (ref "DD1") (pin "J2") (pinfunction "LVDS34p_J2") (pintype "passive"))
    )
    (net (code "334") (name "unconnected-(DD1P-LVDS35n-PadH1)") (class "Default")
      (node (ref "DD1") (pin "H1") (pinfunction "LVDS35n_H1") (pintype "passive"))
    )
    (net (code "335") (name "unconnected-(DD1P-LVDS35p-PadH2)") (class "Default")
      (node (ref "DD1") (pin "H2") (pinfunction "LVDS35p_H2") (pintype "passive"))
    )
    (net (code "336") (name "unconnected-(DD1P-LVDS36n-PadJ4)") (class "Default")
      (node (ref "DD1") (pin "J4") (pinfunction "LVDS36n_J4") (pintype "passive"))
    )
    (net (code "337") (name "unconnected-(DD1P-LVDS36p-PadJ3)") (class "Default")
      (node (ref "DD1") (pin "J3") (pinfunction "LVDS36p_J3") (pintype "passive"))
    )
    (net (code "338") (name "unconnected-(DD1P-LVDS37n-PadH4)") (class "Default")
      (node (ref "DD1") (pin "H4") (pinfunction "LVDS37n_H4") (pintype "passive"))
    )
    (net (code "339") (name "unconnected-(DD1P-LVDS37p-PadH3)") (class "Default")
      (node (ref "DD1") (pin "H3") (pinfunction "LVDS37p_H3") (pintype "passive"))
    )
    (net (code "340") (name "unconnected-(DD1P-LVDS38n-PadG2)") (class "Default")
      (node (ref "DD1") (pin "G2") (pinfunction "LVDS38n_G2") (pintype "passive"))
    )
    (net (code "341") (name "unconnected-(DD1P-LVDS38p-PadG1)") (class "Default")
      (node (ref "DD1") (pin "G1") (pinfunction "LVDS38p_G1") (pintype "passive"))
    )
    (net (code "342") (name "unconnected-(DD1P-LVDS39n-PadF1)") (class "Default")
      (node (ref "DD1") (pin "F1") (pinfunction "LVDS39n_F1") (pintype "passive"))
    )
    (net (code "343") (name "unconnected-(DD1P-LVDS39p-PadF2)") (class "Default")
      (node (ref "DD1") (pin "F2") (pinfunction "LVDS39p_F2") (pintype "passive"))
    )
    (net (code "344") (name "unconnected-(DD1Q-CL0-PadN2)") (class "Default")
      (node (ref "DD1") (pin "N2") (pinfunction "CL0_N2") (pintype "passive"))
    )
    (net (code "345") (name "unconnected-(DD1Q-IO2_0-PadF7)") (class "Default")
      (node (ref "DD1") (pin "F7") (pinfunction "IO2_0_F7") (pintype "passive"))
    )
    (net (code "346") (name "unconnected-(DD1Q-IO2_1-PadH6)") (class "Default")
      (node (ref "DD1") (pin "H6") (pinfunction "IO2_1_H6") (pintype "passive"))
    )
    (net (code "347") (name "unconnected-(DD1Q-IO2_2-PadJ6)") (class "Default")
      (node (ref "DD1") (pin "J6") (pinfunction "IO2_2_J6") (pintype "passive"))
    )
    (net (code "348") (name "unconnected-(DD1Q-IO2_4-PadL10)") (class "Default")
      (node (ref "DD1") (pin "L10") (pinfunction "IO2_4_L10") (pintype "passive"))
    )
    (net (code "349") (name "unconnected-(DD1Q-LVDS40n-PadK7)") (class "Default")
      (node (ref "DD1") (pin "K7") (pinfunction "LVDS40n_K7") (pintype "passive"))
    )
    (net (code "350") (name "unconnected-(DD1Q-LVDS40p-PadK8)") (class "Default")
      (node (ref "DD1") (pin "K8") (pinfunction "LVDS40p_K8") (pintype "passive"))
    )
    (net (code "351") (name "unconnected-(DD1Q-LVDS41n-PadG3)") (class "Default")
      (node (ref "DD1") (pin "G3") (pinfunction "LVDS41n_G3") (pintype "passive"))
    )
    (net (code "352") (name "unconnected-(DD1Q-LVDS41p-PadG4)") (class "Default")
      (node (ref "DD1") (pin "G4") (pinfunction "LVDS41p_G4") (pintype "passive"))
    )
    (net (code "353") (name "unconnected-(DD1Q-LVDS42n-PadK5)") (class "Default")
      (node (ref "DD1") (pin "K5") (pinfunction "LVDS42n_K5") (pintype "passive"))
    )
    (net (code "354") (name "unconnected-(DD1Q-LVDS42p-PadK6)") (class "Default")
      (node (ref "DD1") (pin "K6") (pinfunction "LVDS42p_K6") (pintype "passive"))
    )
    (net (code "355") (name "unconnected-(DD1Q-LVDS43p-PadE2)") (class "Default")
      (node (ref "DD1") (pin "E2") (pinfunction "LVDS43p_E2") (pintype "passive"))
    )
    (net (code "356") (name "unconnected-(DD1Q-LVDS44n-PadJ7)") (class "Default")
      (node (ref "DD1") (pin "J7") (pinfunction "LVDS44n_J7") (pintype "passive"))
    )
    (net (code "357") (name "unconnected-(DD1Q-LVDS44p-PadJ8)") (class "Default")
      (node (ref "DD1") (pin "J8") (pinfunction "LVDS44p_J8") (pintype "passive"))
    )
    (net (code "358") (name "unconnected-(DD1Q-LVDS45p-PadD2)") (class "Default")
      (node (ref "DD1") (pin "D2") (pinfunction "LVDS45p_D2") (pintype "passive"))
    )
    (net (code "359") (name "unconnected-(DD1Q-LVDS46n-PadF4)") (class "Default")
      (node (ref "DD1") (pin "F4") (pinfunction "LVDS46n_F4") (pintype "passive"))
    )
    (net (code "360") (name "unconnected-(DD1Q-LVDS46p-PadF3)") (class "Default")
      (node (ref "DD1") (pin "F3") (pinfunction "LVDS46p_F3") (pintype "passive"))
    )
    (net (code "361") (name "unconnected-(DD1Q-LVDS47n-PadG6)") (class "Default")
      (node (ref "DD1") (pin "G6") (pinfunction "LVDS47n_G6") (pintype "passive"))
    )
    (net (code "362") (name "unconnected-(DD1Q-LVDS47p-PadG5)") (class "Default")
      (node (ref "DD1") (pin "G5") (pinfunction "LVDS47p_G5") (pintype "passive"))
    )
    (net (code "363") (name "unconnected-(DD1Q-LVDS48n-PadC3)") (class "Default")
      (node (ref "DD1") (pin "C3") (pinfunction "LVDS48n_C3") (pintype "passive"))
    )
    (net (code "364") (name "unconnected-(DD1Q-LVDS48p-PadC2)") (class "Default")
      (node (ref "DD1") (pin "C2") (pinfunction "LVDS48p_C2") (pintype "passive"))
    )
    (net (code "365") (name "unconnected-(DD1Q-LVDS49n-PadB3)") (class "Default")
      (node (ref "DD1") (pin "B3") (pinfunction "LVDS49n_B3") (pintype "passive"))
    )
    (net (code "366") (name "unconnected-(DD1Q-LVDS49p-PadB2)") (class "Default")
      (node (ref "DD1") (pin "B2") (pinfunction "LVDS49p_B2") (pintype "passive"))
    )
    (net (code "367") (name "unconnected-(DD1Q-PLL3_OUTn-PadF6)") (class "Default")
      (node (ref "DD1") (pin "F6") (pinfunction "PLL3_OUTn_F6") (pintype "passive"))
    )
    (net (code "368") (name "unconnected-(DD1Q-PLL3_OUTp-PadE5)") (class "Default")
      (node (ref "DD1") (pin "E5") (pinfunction "PLL3_OUTp_E5") (pintype "passive"))
    )
    (net (code "369") (name "unconnected-(DD1Q-VREFB2N0-PadJ5)") (class "Default")
      (node (ref "DD1") (pin "J5") (pinfunction "VREFB2N0_J5") (pintype "passive"))
    )
    (net (code "370") (name "unconnected-(DD1Q-VREFB2N1-PadL4)") (class "Default")
      (node (ref "DD1") (pin "L4") (pinfunction "VREFB2N1_L4") (pintype "passive"))
    )
    (net (code "371") (name "unconnected-(DD1R-IO5_1-PadH21)") (class "Default")
      (node (ref "DD1") (pin "H21") (pinfunction "IO5_1_H21") (pintype "passive"))
    )
    (net (code "372") (name "unconnected-(DD1R-LVDS100n-PadD23)") (class "Default")
      (node (ref "DD1") (pin "D23") (pinfunction "LVDS100n_D23") (pintype "passive"))
    )
    (net (code "373") (name "unconnected-(DD1R-LVDS100p-PadE22)") (class "Default")
      (node (ref "DD1") (pin "E22") (pinfunction "LVDS100p_E22") (pintype "passive"))
    )
    (net (code "374") (name "unconnected-(DD1R-LVDS101n-PadG22)") (class "Default")
      (node (ref "DD1") (pin "G22") (pinfunction "LVDS101n_G22") (pintype "passive"))
    )
    (net (code "375") (name "unconnected-(DD1R-LVDS101p-PadG21)") (class "Default")
      (node (ref "DD1") (pin "G21") (pinfunction "LVDS101p_G21") (pintype "passive"))
    )
    (net (code "376") (name "unconnected-(DD1R-LVDS102n-PadE24)") (class "Default")
      (node (ref "DD1") (pin "E24") (pinfunction "LVDS102n_E24") (pintype "passive"))
    )
    (net (code "377") (name "unconnected-(DD1R-LVDS102p-PadE23)") (class "Default")
      (node (ref "DD1") (pin "E23") (pinfunction "LVDS102p_E23") (pintype "passive"))
    )
    (net (code "378") (name "unconnected-(DD1R-LVDS103n-PadB25)") (class "Default")
      (node (ref "DD1") (pin "B25") (pinfunction "LVDS103n_B25") (pintype "passive"))
    )
    (net (code "379") (name "unconnected-(DD1R-LVDS103p-PadB24)") (class "Default")
      (node (ref "DD1") (pin "B24") (pinfunction "LVDS103p_B24") (pintype "passive"))
    )
    (net (code "380") (name "unconnected-(DD1R-LVDS104n-PadC24)") (class "Default")
      (node (ref "DD1") (pin "C24") (pinfunction "LVDS104n_C24") (pintype "passive"))
    )
    (net (code "381") (name "unconnected-(DD1R-LVDS104p-PadC25)") (class "Default")
      (node (ref "DD1") (pin "C25") (pinfunction "LVDS104p_C25") (pintype "passive"))
    )
    (net (code "382") (name "unconnected-(DD1R-LVDS105n-PadD25)") (class "Default")
      (node (ref "DD1") (pin "D25") (pinfunction "LVDS105n_D25") (pintype "passive"))
    )
    (net (code "383") (name "unconnected-(DD1R-LVDS106n-PadE25)") (class "Default")
      (node (ref "DD1") (pin "E25") (pinfunction "LVDS106n_E25") (pintype "passive"))
    )
    (net (code "384") (name "unconnected-(DD1R-LVDS107n-PadF23)") (class "Default")
      (node (ref "DD1") (pin "F23") (pinfunction "LVDS107n_F23") (pintype "passive"))
    )
    (net (code "385") (name "unconnected-(DD1R-LVDS107p-PadF24)") (class "Default")
      (node (ref "DD1") (pin "F24") (pinfunction "LVDS107p_F24") (pintype "passive"))
    )
    (net (code "386") (name "unconnected-(DD1R-LVDS108n-PadJ20)") (class "Default")
      (node (ref "DD1") (pin "J20") (pinfunction "LVDS108n_J20") (pintype "passive"))
    )
    (net (code "387") (name "unconnected-(DD1R-LVDS108p-PadJ21)") (class "Default")
      (node (ref "DD1") (pin "J21") (pinfunction "LVDS108p_J21") (pintype "passive"))
    )
    (net (code "388") (name "unconnected-(DD1R-LVDS109p-PadF25)") (class "Default")
      (node (ref "DD1") (pin "F25") (pinfunction "LVDS109p_F25") (pintype "passive"))
    )
    (net (code "389") (name "unconnected-(DD1R-LVDS110n-PadP18)") (class "Default")
      (node (ref "DD1") (pin "P18") (pinfunction "LVDS110n_P18") (pintype "passive"))
    )
    (net (code "390") (name "unconnected-(DD1R-LVDS110p-PadN18)") (class "Default")
      (node (ref "DD1") (pin "N18") (pinfunction "LVDS110p_N18") (pintype "passive"))
    )
    (net (code "391") (name "unconnected-(DD1R-LVDS111n-PadG24)") (class "Default")
      (node (ref "DD1") (pin "G24") (pinfunction "LVDS111n_G24") (pintype "passive"))
    )
    (net (code "392") (name "unconnected-(DD1R-LVDS111p-PadG23)") (class "Default")
      (node (ref "DD1") (pin "G23") (pinfunction "LVDS111p_G23") (pintype "passive"))
    )
    (net (code "393") (name "unconnected-(DD1R-LVDS112p-PadG25)") (class "Default")
      (node (ref "DD1") (pin "G25") (pinfunction "LVDS112p_G25") (pintype "passive"))
    )
    (net (code "394") (name "unconnected-(DD1R-LVDS120n-PadL25)") (class "Default")
      (node (ref "DD1") (pin "L25") (pinfunction "LVDS120n_L25") (pintype "passive"))
    )
    (net (code "395") (name "unconnected-(DD1R-LVDS120p-PadL24)") (class "Default")
      (node (ref "DD1") (pin "L24") (pinfunction "LVDS120p_L24") (pintype "passive"))
    )
    (net (code "396") (name "unconnected-(DD1R-LVDS126p-PadN23)") (class "Default")
      (node (ref "DD1") (pin "N23") (pinfunction "LVDS126p_N23") (pintype "passive"))
    )
    (net (code "397") (name "unconnected-(DD1R-LVDS127p-PadP23)") (class "Default")
      (node (ref "DD1") (pin "P23") (pinfunction "LVDS127p_P23") (pintype "passive"))
    )
    (net (code "398") (name "unconnected-(DD1S-CLK4-PadN25)") (class "Default")
      (node (ref "DD1") (pin "N25") (pinfunction "CLK4_N25") (pintype "passive"))
    )
    (net (code "399") (name "unconnected-(DD1S-CLK6-PadP25)") (class "Default")
      (node (ref "DD1") (pin "P25") (pinfunction "CLK6_P25") (pintype "passive"))
    )
    (net (code "400") (name "unconnected-(DD1S-IO5_0-PadH19)") (class "Default")
      (node (ref "DD1") (pin "H19") (pinfunction "IO5_0_H19") (pintype "passive"))
    )
    (net (code "401") (name "unconnected-(DD1S-IO5_2-PadK21)") (class "Default")
      (node (ref "DD1") (pin "K21") (pinfunction "IO5_2_K21") (pintype "passive"))
    )
    (net (code "402") (name "unconnected-(DD1S-IO5_3-PadK22)") (class "Default")
      (node (ref "DD1") (pin "K22") (pinfunction "IO5_3_K22") (pintype "passive"))
    )
    (net (code "403") (name "unconnected-(DD1S-IO5_4-PadL19)") (class "Default")
      (node (ref "DD1") (pin "L19") (pinfunction "IO5_4_L19") (pintype "passive"))
    )
    (net (code "404") (name "unconnected-(DD1S-IO6_3-PadY21)") (class "Default")
      (node (ref "DD1") (pin "Y21") (pinfunction "IO6_3_Y21") (pintype "passive"))
    )
    (net (code "405") (name "unconnected-(DD1S-IO6_4-PadAC23)") (class "Default")
      (node (ref "DD1") (pin "AC23") (pinfunction "IO6_4_AC23") (pintype "passive"))
    )
    (net (code "406") (name "unconnected-(DD1S-LVDS113n-PadH24)") (class "Default")
      (node (ref "DD1") (pin "H24") (pinfunction "LVDS113n_H24") (pintype "passive"))
    )
    (net (code "407") (name "unconnected-(DD1S-LVDS113p-PadH23)") (class "Default")
      (node (ref "DD1") (pin "H23") (pinfunction "LVDS113p_H23") (pintype "passive"))
    )
    (net (code "408") (name "unconnected-(DD1S-LVDS114n-PadJ24)") (class "Default")
      (node (ref "DD1") (pin "J24") (pinfunction "LVDS114n_J24") (pintype "passive"))
    )
    (net (code "409") (name "unconnected-(DD1S-LVDS114p-PadJ23)") (class "Default")
      (node (ref "DD1") (pin "J23") (pinfunction "LVDS114p_J23") (pintype "passive"))
    )
    (net (code "410") (name "unconnected-(DD1S-LVDS115p-PadH25)") (class "Default")
      (node (ref "DD1") (pin "H25") (pinfunction "LVDS115p_H25") (pintype "passive"))
    )
    (net (code "411") (name "unconnected-(DD1S-LVDS116n-PadK19)") (class "Default")
      (node (ref "DD1") (pin "K19") (pinfunction "LVDS116n_K19") (pintype "passive"))
    )
    (net (code "412") (name "unconnected-(DD1S-LVDS116p-PadK18)") (class "Default")
      (node (ref "DD1") (pin "K18") (pinfunction "LVDS116p_K18") (pintype "passive"))
    )
    (net (code "413") (name "unconnected-(DD1S-LVDS117n-PadK24)") (class "Default")
      (node (ref "DD1") (pin "K24") (pinfunction "LVDS117n_K24") (pintype "passive"))
    )
    (net (code "414") (name "unconnected-(DD1S-LVDS117p-PadK23)") (class "Default")
      (node (ref "DD1") (pin "K23") (pinfunction "LVDS117p_K23") (pintype "passive"))
    )
    (net (code "415") (name "unconnected-(DD1S-LVDS118n-PadL20)") (class "Default")
      (node (ref "DD1") (pin "L20") (pinfunction "LVDS118n_L20") (pintype "passive"))
    )
    (net (code "416") (name "unconnected-(DD1S-LVDS118p-PadL21)") (class "Default")
      (node (ref "DD1") (pin "L21") (pinfunction "LVDS118p_L21") (pintype "passive"))
    )
    (net (code "417") (name "unconnected-(DD1S-LVDS119p-PadJ25)") (class "Default")
      (node (ref "DD1") (pin "J25") (pinfunction "LVDS119p_J25") (pintype "passive"))
    )
    (net (code "418") (name "unconnected-(DD1S-LVDS130n-PadP17)") (class "Default")
      (node (ref "DD1") (pin "P17") (pinfunction "LVDS130n_P17") (pintype "passive"))
    )
    (net (code "419") (name "unconnected-(DD1S-LVDS131p-PadR17)") (class "Default")
      (node (ref "DD1") (pin "R17") (pinfunction "LVDS131p_R17") (pintype "passive"))
    )
    (net (code "420") (name "unconnected-(DD1S-LVDS133n-PadT17)") (class "Default")
      (node (ref "DD1") (pin "T17") (pinfunction "LVDS133n_T17") (pintype "passive"))
    )
    (net (code "421") (name "unconnected-(DD1S-LVDS149n-PadAD25)") (class "Default")
      (node (ref "DD1") (pin "AD25") (pinfunction "LVDS149n_AD25") (pintype "passive"))
    )
    (net (code "422") (name "unconnected-(DD1S-LVDS149p-PadAD24)") (class "Default")
      (node (ref "DD1") (pin "AD24") (pinfunction "LVDS149p_AD24") (pintype "passive"))
    )
    (net (code "423") (name "unconnected-(DD1S-PLL2_OUTn-PadF20)") (class "Default")
      (node (ref "DD1") (pin "F20") (pinfunction "PLL2_OUTn_F20") (pintype "passive"))
    )
    (net (code "424") (name "unconnected-(DD1S-PLL2_OUTp-PadF21)") (class "Default")
      (node (ref "DD1") (pin "F21") (pinfunction "PLL2_OUTp_F21") (pintype "passive"))
    )
    (net (code "425") (name "unconnected-(DD1S-VREFB5N0-PadJ22)") (class "Default")
      (node (ref "DD1") (pin "J22") (pinfunction "VREFB5N0_J22") (pintype "passive"))
    )
    (net (code "426") (name "unconnected-(DD1S-VREFB5N1-PadL23)") (class "Default")
      (node (ref "DD1") (pin "L23") (pinfunction "VREFB5N1_L23") (pintype "passive"))
    )
    (net (code "427") (name "unconnected-(DD1T-LVDS127n-PadP24)") (class "Default")
      (node (ref "DD1") (pin "P24") (pinfunction "LVDS127n_P24") (pintype "passive"))
    )
    (net (code "428") (name "unconnected-(DD1T-LVDS128n-PadR24)") (class "Default")
      (node (ref "DD1") (pin "R24") (pinfunction "LVDS128n_R24") (pintype "passive"))
    )
    (net (code "429") (name "unconnected-(DD1T-LVDS128p-PadR25)") (class "Default")
      (node (ref "DD1") (pin "R25") (pinfunction "LVDS128p_R25") (pintype "passive"))
    )
    (net (code "430") (name "unconnected-(DD1T-LVDS129n-PadT23)") (class "Default")
      (node (ref "DD1") (pin "T23") (pinfunction "LVDS129n_T23") (pintype "passive"))
    )
    (net (code "431") (name "unconnected-(DD1T-LVDS129p-PadT22)") (class "Default")
      (node (ref "DD1") (pin "T22") (pinfunction "LVDS129p_T22") (pintype "passive"))
    )
    (net (code "432") (name "unconnected-(DD1T-LVDS132n-PadT25)") (class "Default")
      (node (ref "DD1") (pin "T25") (pinfunction "LVDS132n_T25") (pintype "passive"))
    )
    (net (code "433") (name "unconnected-(DD1T-LVDS132p-PadT24)") (class "Default")
      (node (ref "DD1") (pin "T24") (pinfunction "LVDS132p_T24") (pintype "passive"))
    )
    (net (code "434") (name "unconnected-(DD1T-LVDS133p-PadT18)") (class "Default")
      (node (ref "DD1") (pin "T18") (pinfunction "LVDS133p_T18") (pintype "passive"))
    )
    (net (code "435") (name "unconnected-(DD1T-LVDS134n-PadU25)") (class "Default")
      (node (ref "DD1") (pin "U25") (pinfunction "LVDS134n_U25") (pintype "passive"))
    )
    (net (code "436") (name "unconnected-(DD1T-LVDS135n-PadU24)") (class "Default")
      (node (ref "DD1") (pin "U24") (pinfunction "LVDS135n_U24") (pintype "passive"))
    )
    (net (code "437") (name "unconnected-(DD1T-LVDS135p-PadR19)") (class "Default")
      (node (ref "DD1") (pin "R19") (pinfunction "LVDS135p_R19") (pintype "passive"))
    )
    (net (code "438") (name "unconnected-(DD1T-LVDS135p-PadU23)") (class "Default")
      (node (ref "DD1") (pin "U23") (pinfunction "LVDS135p_U23") (pintype "passive"))
    )
    (net (code "439") (name "unconnected-(DD1T-LVDS136n-PadT19)") (class "Default")
      (node (ref "DD1") (pin "T19") (pinfunction "LVDS136n_T19") (pintype "passive"))
    )
    (net (code "440") (name "unconnected-(DD1T-LVDS136n-PadU21)") (class "Default")
      (node (ref "DD1") (pin "U21") (pinfunction "LVDS136n_U21") (pintype "passive"))
    )
    (net (code "441") (name "unconnected-(DD1T-LVDS143n-PadY24)") (class "Default")
      (node (ref "DD1") (pin "Y24") (pinfunction "LVDS143n_Y24") (pintype "passive"))
    )
    (net (code "442") (name "unconnected-(DD1T-LVDS144p-PadAB25)") (class "Default")
      (node (ref "DD1") (pin "AB25") (pinfunction "LVDS144p_AB25") (pintype "passive"))
    )
    (net (code "443") (name "unconnected-(DD1T-LVDS145n-PadAC25)") (class "Default")
      (node (ref "DD1") (pin "AC25") (pinfunction "LVDS145n_AC25") (pintype "passive"))
    )
    (net (code "444") (name "unconnected-(DD1T-LVDS146n-PadAB24)") (class "Default")
      (node (ref "DD1") (pin "AB24") (pinfunction "LVDS146n_AB24") (pintype "passive"))
    )
    (net (code "445") (name "unconnected-(DD1T-LVDS146p-PadAB23)") (class "Default")
      (node (ref "DD1") (pin "AB23") (pinfunction "LVDS146p_AB23") (pintype "passive"))
    )
    (net (code "446") (name "unconnected-(DD1T-LVDS147n-PadAA24)") (class "Default")
      (node (ref "DD1") (pin "AA24") (pinfunction "LVDS147n_AA24") (pintype "passive"))
    )
    (net (code "447") (name "unconnected-(DD1T-LVDS147p-PadAA23)") (class "Default")
      (node (ref "DD1") (pin "AA23") (pinfunction "LVDS147p_AA23") (pintype "passive"))
    )
    (net (code "448") (name "unconnected-(DD1T-LVDS148n-PadW21)") (class "Default")
      (node (ref "DD1") (pin "W21") (pinfunction "LVDS148n_W21") (pintype "passive"))
    )
    (net (code "449") (name "unconnected-(DD1T-LVDS148p-PadY22)") (class "Default")
      (node (ref "DD1") (pin "Y22") (pinfunction "LVDS148p_Y22") (pintype "passive"))
    )
    (net (code "450") (name "unconnected-(DD1T-PLL4_OUTn-PadV20)") (class "Default")
      (node (ref "DD1") (pin "V20") (pinfunction "PLL4_OUTn_V20") (pintype "passive"))
    )
    (net (code "451") (name "unconnected-(DD1T-PLL4_OUTp-PadV21)") (class "Default")
      (node (ref "DD1") (pin "V21") (pinfunction "PLL4_OUTp_V21") (pintype "passive"))
    )
    (net (code "452") (name "unconnected-(DD1T-VREFB6N0-PadT21)") (class "Default")
      (node (ref "DD1") (pin "T21") (pinfunction "VREFB6N0_T21") (pintype "passive"))
    )
    (net (code "453") (name "unconnected-(DD1T-VREFB6N1-PadV22)") (class "Default")
      (node (ref "DD1") (pin "V22") (pinfunction "VREFB6N1_V22") (pintype "passive"))
    )
    (net (code "454") (name "unconnected-(DD1U-IO6_0-PadR20)") (class "Default")
      (node (ref "DD1") (pin "R20") (pinfunction "IO6_0_R20") (pintype "passive"))
    )
    (net (code "455") (name "unconnected-(DD1U-IO6_1-PadT20)") (class "Default")
      (node (ref "DD1") (pin "T20") (pinfunction "IO6_1_T20") (pintype "passive"))
    )
    (net (code "456") (name "unconnected-(DD1U-IO6_2-PadU22)") (class "Default")
      (node (ref "DD1") (pin "U22") (pinfunction "IO6_2_U22") (pintype "passive"))
    )
    (net (code "457") (name "unconnected-(DD1U-LVDS121p-PadK25)") (class "Default")
      (node (ref "DD1") (pin "K25") (pinfunction "LVDS121p_K25") (pintype "passive"))
    )
    (net (code "458") (name "unconnected-(DD1U-LVDS122n-PadM23)") (class "Default")
      (node (ref "DD1") (pin "M23") (pinfunction "LVDS122n_M23") (pintype "passive"))
    )
    (net (code "459") (name "unconnected-(DD1U-LVDS122p-PadM22)") (class "Default")
      (node (ref "DD1") (pin "M22") (pinfunction "LVDS122p_M22") (pintype "passive"))
    )
    (net (code "460") (name "unconnected-(DD1U-LVDS123n-PadM20)") (class "Default")
      (node (ref "DD1") (pin "M20") (pinfunction "LVDS123n_M20") (pintype "passive"))
    )
    (net (code "461") (name "unconnected-(DD1U-LVDS123p-PadM19)") (class "Default")
      (node (ref "DD1") (pin "M19") (pinfunction "LVDS123p_M19") (pintype "passive"))
    )
    (net (code "462") (name "unconnected-(DD1U-LVDS124n-PadM21)") (class "Default")
      (node (ref "DD1") (pin "M21") (pinfunction "LVDS124n_M21") (pintype "passive"))
    )
    (net (code "463") (name "unconnected-(DD1U-LVDS124p-PadN20)") (class "Default")
      (node (ref "DD1") (pin "N20") (pinfunction "LVDS124p_N20") (pintype "passive"))
    )
    (net (code "464") (name "unconnected-(DD1U-LVDS125n-PadM25)") (class "Default")
      (node (ref "DD1") (pin "M25") (pinfunction "LVDS125n_M25") (pintype "passive"))
    )
    (net (code "465") (name "unconnected-(DD1U-LVDS125p-PadM24)") (class "Default")
      (node (ref "DD1") (pin "M24") (pinfunction "LVDS125p_M24") (pintype "passive"))
    )
    (net (code "466") (name "unconnected-(DD1U-LVDS126n-PadN24)") (class "Default")
      (node (ref "DD1") (pin "N24") (pinfunction "LVDS126n_N24") (pintype "passive"))
    )
    (net (code "467") (name "unconnected-(DD1U-LVDS136p-PadU20)") (class "Default")
      (node (ref "DD1") (pin "U20") (pinfunction "LVDS136p_U20") (pintype "passive"))
    )
    (net (code "468") (name "unconnected-(DD1U-LVDS137n-PadV25)") (class "Default")
      (node (ref "DD1") (pin "V25") (pinfunction "LVDS137n_V25") (pintype "passive"))
    )
    (net (code "469") (name "unconnected-(DD1U-LVDS138n-PadV23)") (class "Default")
      (node (ref "DD1") (pin "V23") (pinfunction "LVDS138n_V23") (pintype "passive"))
    )
    (net (code "470") (name "unconnected-(DD1U-LVDS138p-PadV24)") (class "Default")
      (node (ref "DD1") (pin "V24") (pinfunction "LVDS138p_V24") (pintype "passive"))
    )
    (net (code "471") (name "unconnected-(DD1U-LVDS139n-PadW25)") (class "Default")
      (node (ref "DD1") (pin "W25") (pinfunction "LVDS139n_W25") (pintype "passive"))
    )
    (net (code "472") (name "unconnected-(DD1U-LVDS140n-PadW24)") (class "Default")
      (node (ref "DD1") (pin "W24") (pinfunction "LVDS140n_W24") (pintype "passive"))
    )
    (net (code "473") (name "unconnected-(DD1U-LVDS140p-PadW23)") (class "Default")
      (node (ref "DD1") (pin "W23") (pinfunction "LVDS140p_W23") (pintype "passive"))
    )
    (net (code "474") (name "unconnected-(DD1U-LVDS141p-PadY25)") (class "Default")
      (node (ref "DD1") (pin "Y25") (pinfunction "LVDS141p_Y25") (pintype "passive"))
    )
    (net (code "475") (name "unconnected-(DD1U-LVDS142n-PadAA25)") (class "Default")
      (node (ref "DD1") (pin "AA25") (pinfunction "LVDS142n_AA25") (pintype "passive"))
    )
    (net (code "476") (name "unconnected-(DD1U-LVDS143p-PadY23)") (class "Default")
      (node (ref "DD1") (pin "Y23") (pinfunction "LVDS143p_Y23") (pintype "passive"))
    )
    (net (code "477") (name "unconnected-(IC1-(MSB)_DB13-Pad1)") (class "Default")
      (node (ref "IC1") (pin "1") (pinfunction "(MSB)_DB13_1") (pintype "passive"))
    )
    (net (code "478") (name "unconnected-(IC1-ACOM-Pad20)") (class "Default")
      (node (ref "IC1") (pin "20") (pinfunction "ACOM_20") (pintype "passive"))
    )
    (net (code "479") (name "unconnected-(IC1-AVDD-Pad24)") (class "Default")
      (node (ref "IC1") (pin "24") (pinfunction "AVDD_24") (pintype "passive"))
    )
    (net (code "480") (name "unconnected-(IC1-CLOCK-Pad28)") (class "Default")
      (node (ref "IC1") (pin "28") (pinfunction "CLOCK_28") (pintype "passive"))
    )
    (net (code "481") (name "unconnected-(IC1-COMP1-Pad19)") (class "Default")
      (node (ref "IC1") (pin "19") (pinfunction "COMP1_19") (pintype "passive"))
    )
    (net (code "482") (name "unconnected-(IC1-COMP2-Pad23)") (class "Default")
      (node (ref "IC1") (pin "23") (pinfunction "COMP2_23") (pintype "passive"))
    )
    (net (code "483") (name "unconnected-(IC1-DB0-Pad14)") (class "Default")
      (node (ref "IC1") (pin "14") (pinfunction "DB0_14") (pintype "passive"))
    )
    (net (code "484") (name "unconnected-(IC1-DB1-Pad13)") (class "Default")
      (node (ref "IC1") (pin "13") (pinfunction "DB1_13") (pintype "passive"))
    )
    (net (code "485") (name "unconnected-(IC1-DB2-Pad12)") (class "Default")
      (node (ref "IC1") (pin "12") (pinfunction "DB2_12") (pintype "passive"))
    )
    (net (code "486") (name "unconnected-(IC1-DB3-Pad11)") (class "Default")
      (node (ref "IC1") (pin "11") (pinfunction "DB3_11") (pintype "passive"))
    )
    (net (code "487") (name "unconnected-(IC1-DB4-Pad10)") (class "Default")
      (node (ref "IC1") (pin "10") (pinfunction "DB4_10") (pintype "passive"))
    )
    (net (code "488") (name "unconnected-(IC1-DB5-Pad9)") (class "Default")
      (node (ref "IC1") (pin "9") (pinfunction "DB5_9") (pintype "passive"))
    )
    (net (code "489") (name "unconnected-(IC1-DB6-Pad8)") (class "Default")
      (node (ref "IC1") (pin "8") (pinfunction "DB6_8") (pintype "passive"))
    )
    (net (code "490") (name "unconnected-(IC1-DB7-Pad7)") (class "Default")
      (node (ref "IC1") (pin "7") (pinfunction "DB7_7") (pintype "passive"))
    )
    (net (code "491") (name "unconnected-(IC1-DB8-Pad6)") (class "Default")
      (node (ref "IC1") (pin "6") (pinfunction "DB8_6") (pintype "passive"))
    )
    (net (code "492") (name "unconnected-(IC1-DB9-Pad5)") (class "Default")
      (node (ref "IC1") (pin "5") (pinfunction "DB9_5") (pintype "passive"))
    )
    (net (code "493") (name "unconnected-(IC1-DB10-Pad4)") (class "Default")
      (node (ref "IC1") (pin "4") (pinfunction "DB10_4") (pintype "passive"))
    )
    (net (code "494") (name "unconnected-(IC1-DB11-Pad3)") (class "Default")
      (node (ref "IC1") (pin "3") (pinfunction "DB11_3") (pintype "passive"))
    )
    (net (code "495") (name "unconnected-(IC1-DB12-Pad2)") (class "Default")
      (node (ref "IC1") (pin "2") (pinfunction "DB12_2") (pintype "passive"))
    )
    (net (code "496") (name "unconnected-(IC1-DCOM-Pad26)") (class "Default")
      (node (ref "IC1") (pin "26") (pinfunction "DCOM_26") (pintype "passive"))
    )
    (net (code "497") (name "unconnected-(IC1-DVDD-Pad27)") (class "Default")
      (node (ref "IC1") (pin "27") (pinfunction "DVDD_27") (pintype "passive"))
    )
    (net (code "498") (name "unconnected-(IC1-FS_ADJ-Pad18)") (class "Default")
      (node (ref "IC1") (pin "18") (pinfunction "FS_ADJ_18") (pintype "passive"))
    )
    (net (code "499") (name "unconnected-(IC1-IOUTA-Pad22)") (class "Default")
      (node (ref "IC1") (pin "22") (pinfunction "IOUTA_22") (pintype "passive"))
    )
    (net (code "500") (name "unconnected-(IC1-IOUTB-Pad21)") (class "Default")
      (node (ref "IC1") (pin "21") (pinfunction "IOUTB_21") (pintype "passive"))
    )
    (net (code "501") (name "unconnected-(IC1-NC-Pad25)") (class "Default")
      (node (ref "IC1") (pin "25") (pinfunction "NC_25") (pintype "passive"))
    )
    (net (code "502") (name "unconnected-(IC1-REFIO-Pad17)") (class "Default")
      (node (ref "IC1") (pin "17") (pinfunction "REFIO_17") (pintype "passive"))
    )
    (net (code "503") (name "unconnected-(IC1-REFLO-Pad16)") (class "Default")
      (node (ref "IC1") (pin "16") (pinfunction "REFLO_16") (pintype "passive"))
    )
    (net (code "504") (name "unconnected-(IC1-SLEEP-Pad15)") (class "Default")
      (node (ref "IC1") (pin "15") (pinfunction "SLEEP_15") (pintype "passive"))
    )
  )
)
